# Main.net
KiCad netlist of a schematic drawn in EAGLE
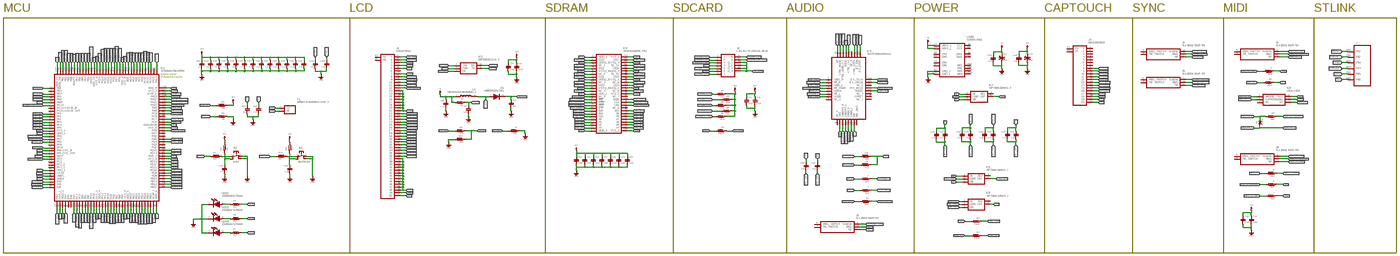
[diagram p0: schematic, sheet 1, overview]
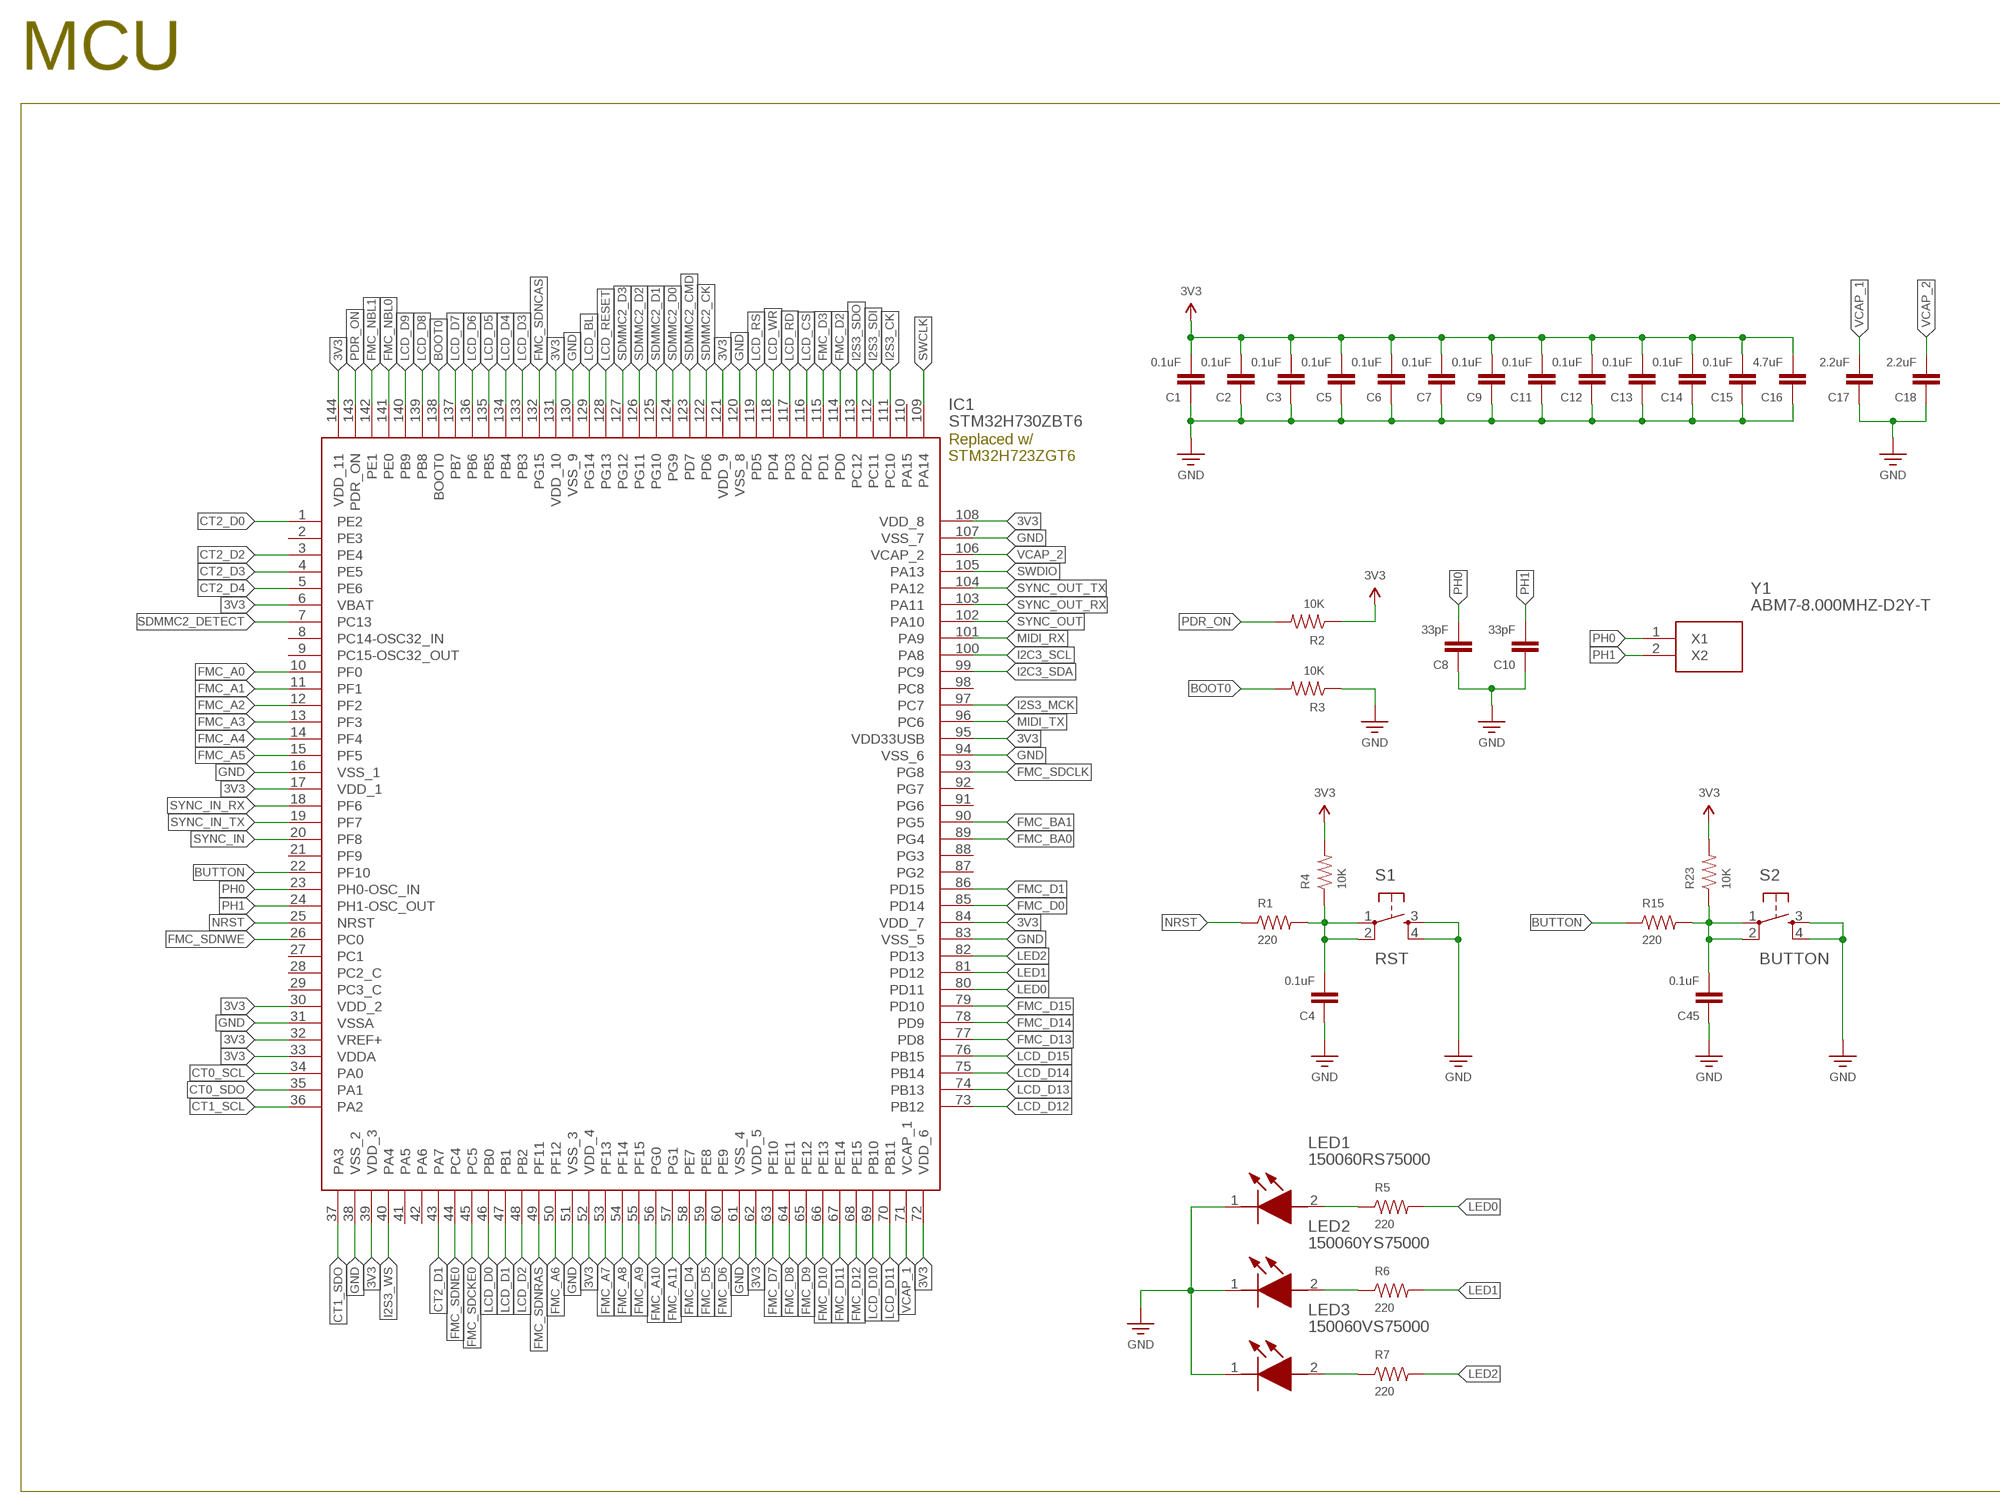
[diagram p1: schematic, sheet 1, part 1 of 4]
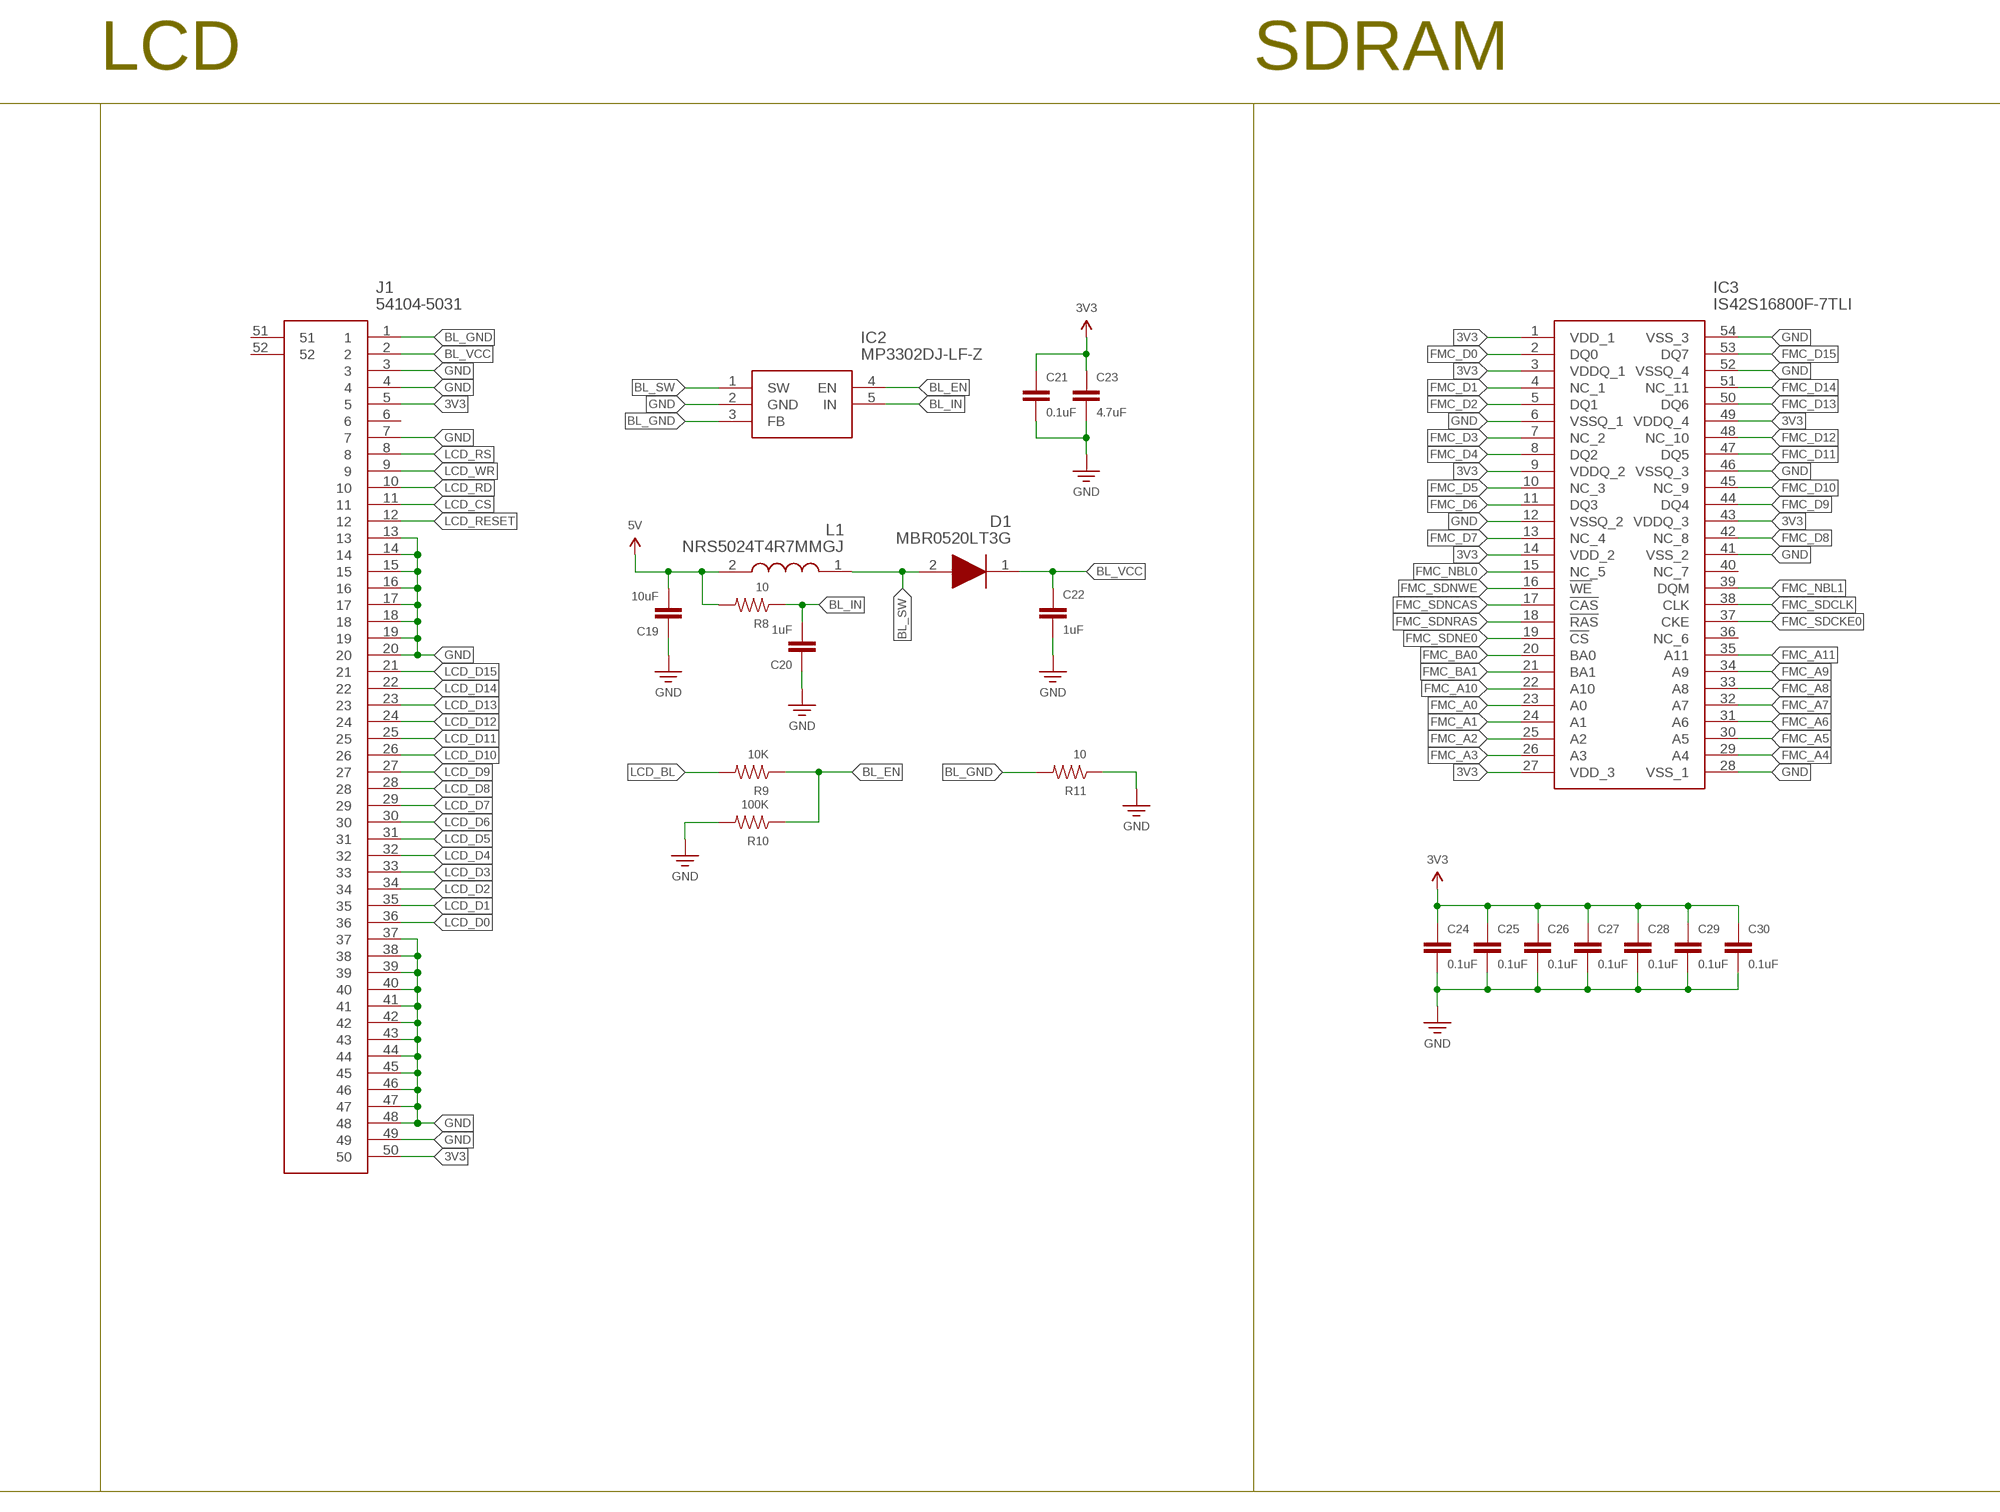
[diagram p2: schematic, sheet 1, part 2 of 4]
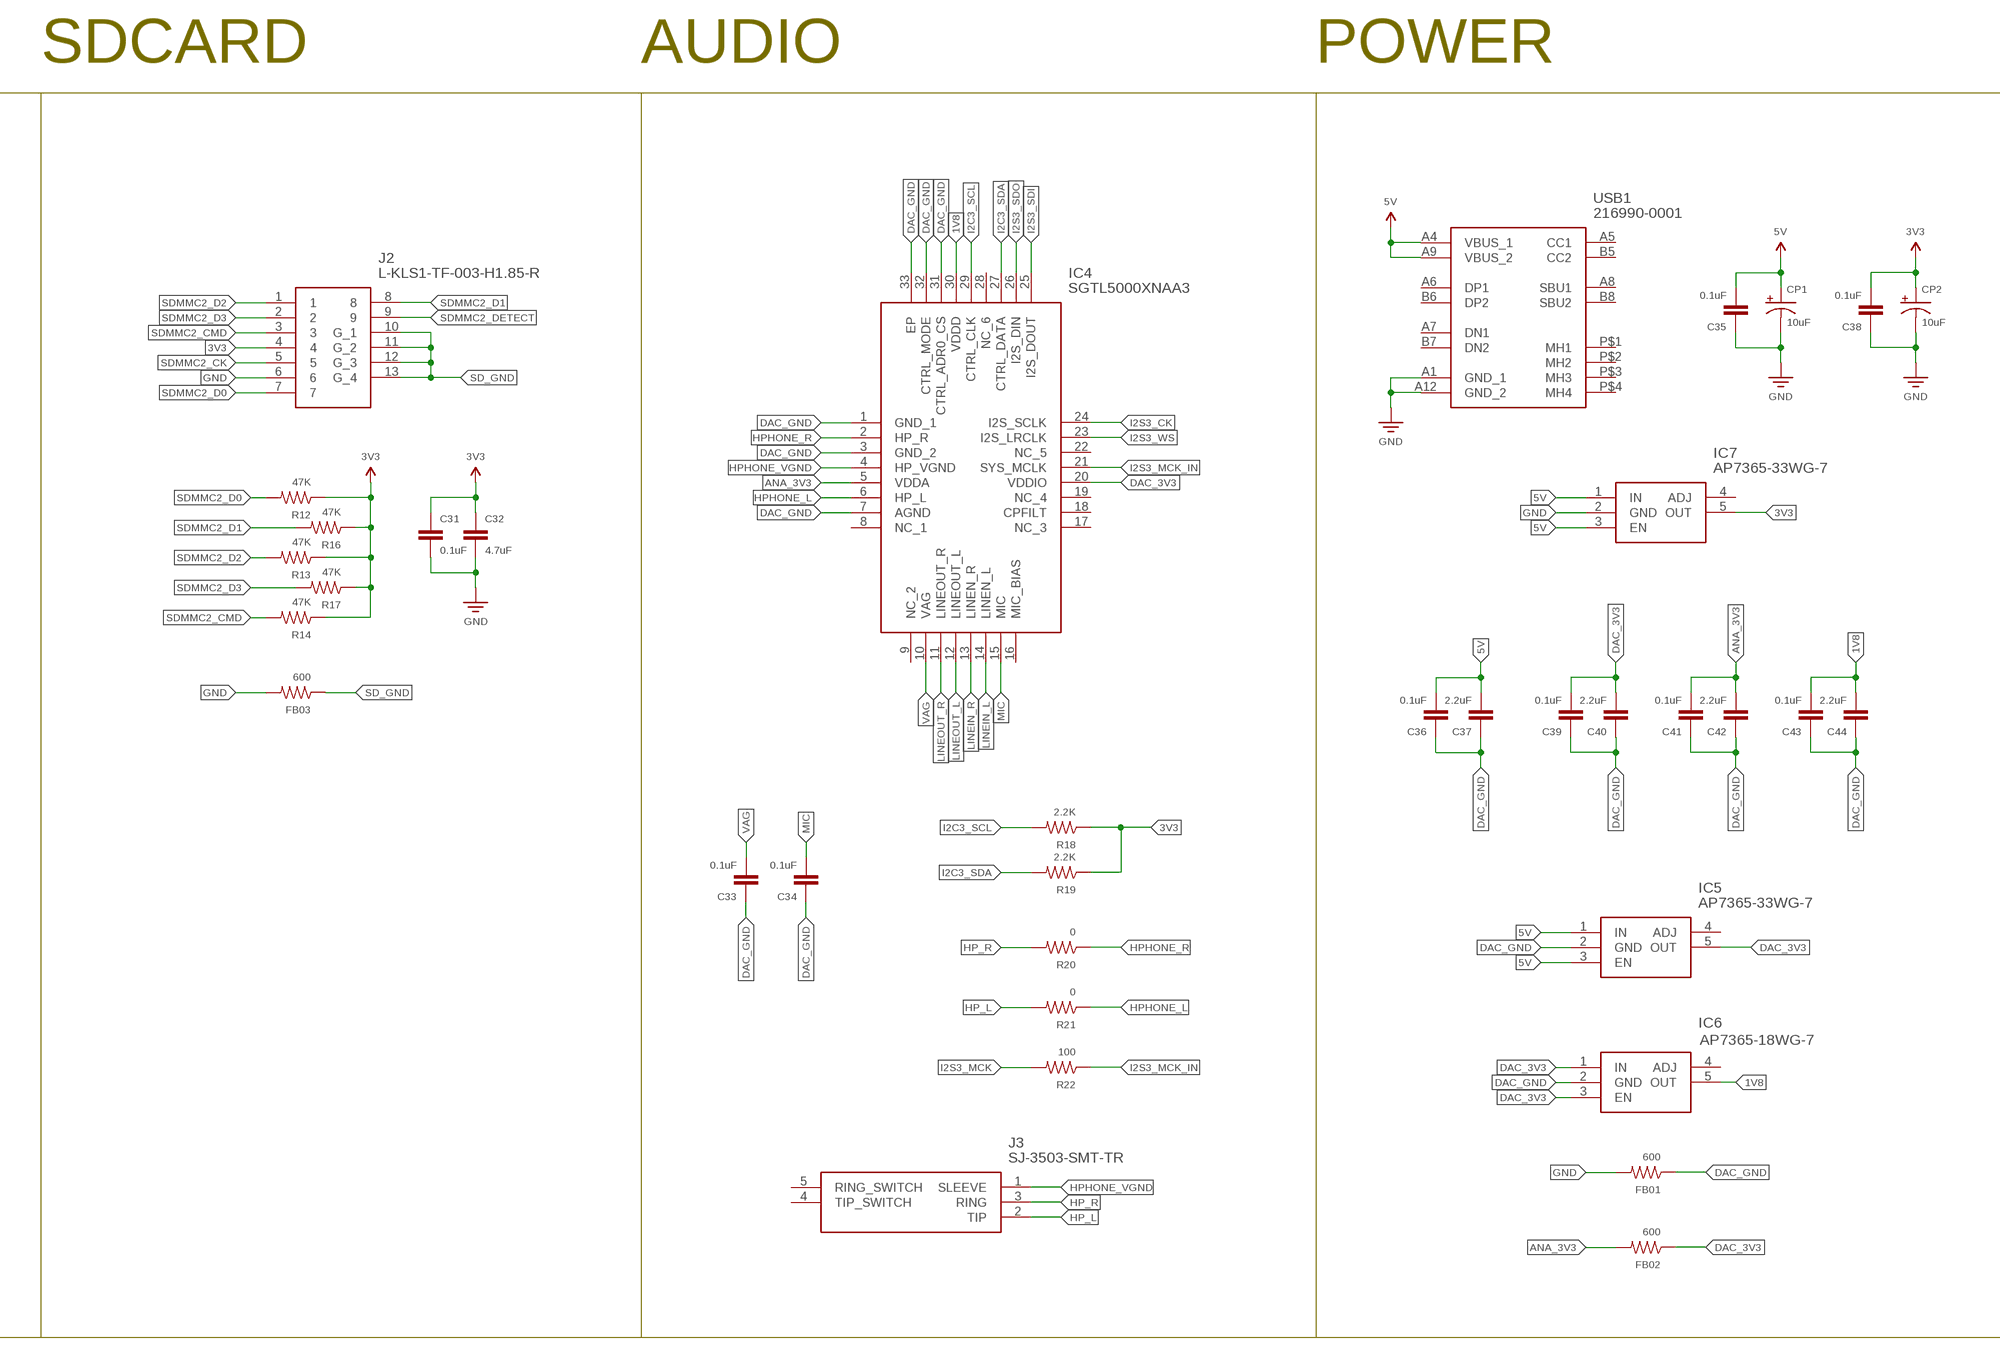
[diagram p3: schematic, sheet 1, part 3 of 4]
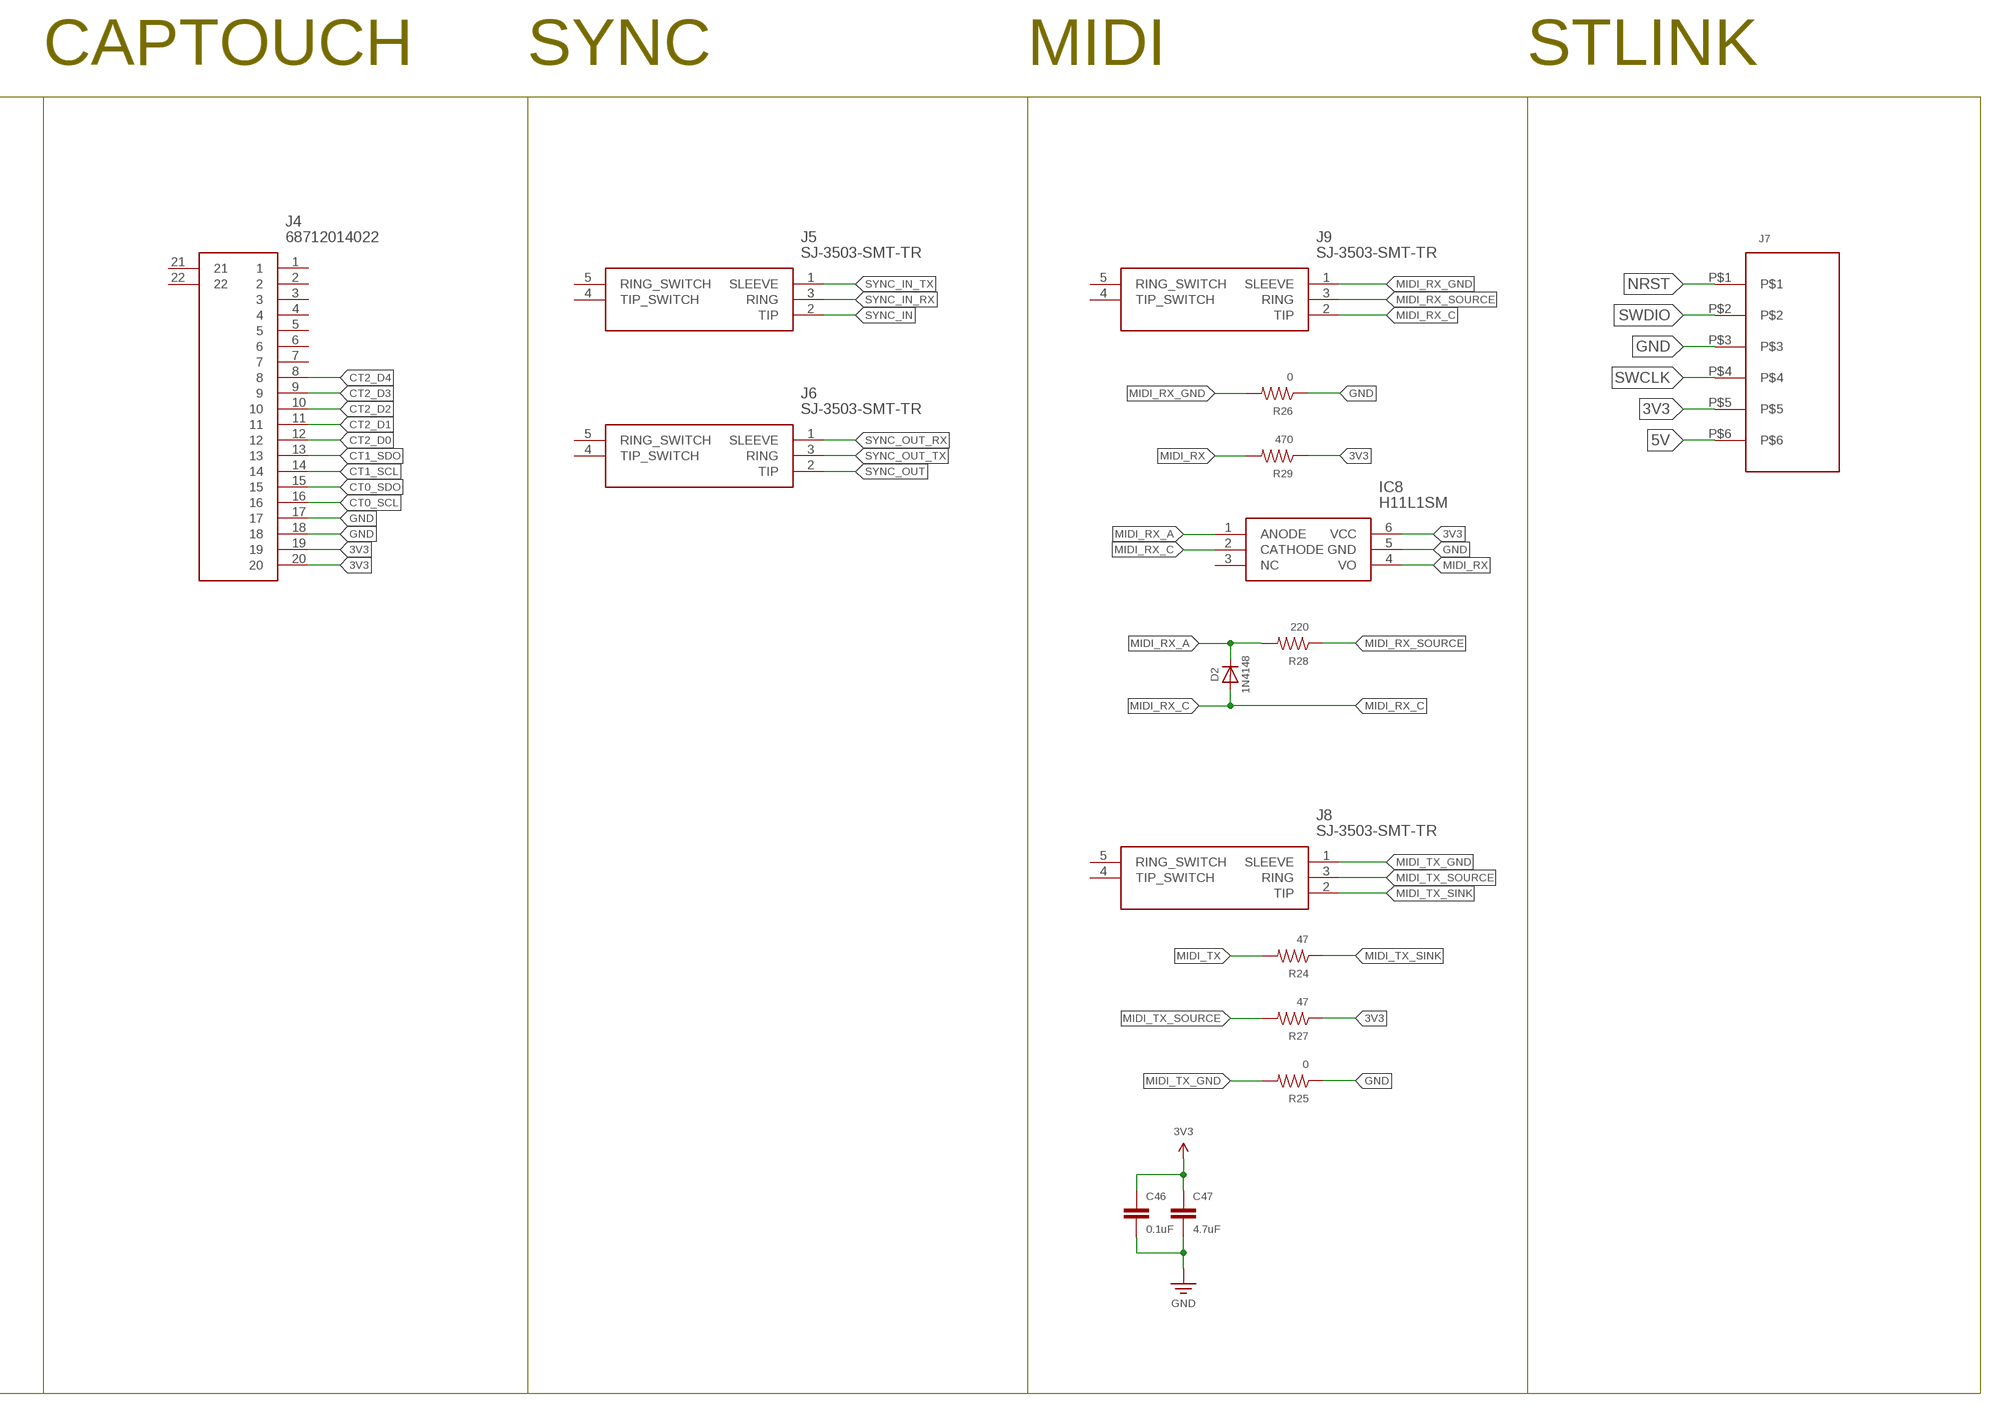
[diagram p4: schematic, sheet 1, part 4 of 4]

(export (version "E")
  (design (tool "Eeschema 10.0.6"))
  (components
    (comp (ref "C1")
      (value "0.1uF")
      (footprint "eagle-import:CAP-0603")
      (libsource (lib "eagle-import") (part "CAP-0603"))
    )
    (comp (ref "C2")
      (value "0.1uF")
      (footprint "eagle-import:CAP-0603")
      (libsource (lib "eagle-import") (part "CAP-0603"))
    )
    (comp (ref "C3")
      (value "0.1uF")
      (footprint "eagle-import:CAP-0603")
      (libsource (lib "eagle-import") (part "CAP-0603"))
    )
    (comp (ref "C4")
      (value "0.1uF")
      (footprint "eagle-import:CAP-0603")
      (libsource (lib "eagle-import") (part "CAP-0603"))
    )
    (comp (ref "C5")
      (value "0.1uF")
      (footprint "eagle-import:CAP-0603")
      (libsource (lib "eagle-import") (part "CAP-0603"))
    )
    (comp (ref "C6")
      (value "0.1uF")
      (footprint "eagle-import:CAP-0603")
      (libsource (lib "eagle-import") (part "CAP-0603"))
    )
    (comp (ref "C7")
      (value "0.1uF")
      (footprint "eagle-import:CAP-0603")
      (libsource (lib "eagle-import") (part "CAP-0603"))
    )
    (comp (ref "C8")
      (value "33pF")
      (footprint "eagle-import:CAP-0603")
      (libsource (lib "eagle-import") (part "CAP-0603"))
    )
    (comp (ref "C9")
      (value "0.1uF")
      (footprint "eagle-import:CAP-0603")
      (libsource (lib "eagle-import") (part "CAP-0603"))
    )
    (comp (ref "C10")
      (value "33pF")
      (footprint "eagle-import:CAP-0603")
      (libsource (lib "eagle-import") (part "CAP-0603"))
    )
    (comp (ref "C11")
      (value "0.1uF")
      (footprint "eagle-import:CAP-0603")
      (libsource (lib "eagle-import") (part "CAP-0603"))
    )
    (comp (ref "C12")
      (value "0.1uF")
      (footprint "eagle-import:CAP-0603")
      (libsource (lib "eagle-import") (part "CAP-0603"))
    )
    (comp (ref "C13")
      (value "0.1uF")
      (footprint "eagle-import:CAP-0603")
      (libsource (lib "eagle-import") (part "CAP-0603"))
    )
    (comp (ref "C14")
      (value "0.1uF")
      (footprint "eagle-import:CAP-0603")
      (libsource (lib "eagle-import") (part "CAP-0603"))
    )
    (comp (ref "C15")
      (value "0.1uF")
      (footprint "eagle-import:CAP-0603")
      (libsource (lib "eagle-import") (part "CAP-0603"))
    )
    (comp (ref "C16")
      (value "4.7uF")
      (footprint "eagle-import:CAP-0603")
      (libsource (lib "eagle-import") (part "CAP-0603"))
    )
    (comp (ref "C17")
      (value "2.2uF")
      (footprint "eagle-import:CAP-0603")
      (libsource (lib "eagle-import") (part "CAP-0603"))
    )
    (comp (ref "C18")
      (value "2.2uF")
      (footprint "eagle-import:CAP-0603")
      (libsource (lib "eagle-import") (part "CAP-0603"))
    )
    (comp (ref "C19")
      (value "10uF")
      (footprint "eagle-import:CAP-0603")
      (libsource (lib "eagle-import") (part "CAP-0603"))
    )
    (comp (ref "C20")
      (value "1uF")
      (footprint "eagle-import:CAP-0603")
      (libsource (lib "eagle-import") (part "CAP-0603"))
    )
    (comp (ref "C21")
      (value "0.1uF")
      (footprint "eagle-import:CAP-0603")
      (libsource (lib "eagle-import") (part "CAP-0603"))
    )
    (comp (ref "C22")
      (value "1uF")
      (footprint "eagle-import:CAP-0603")
      (libsource (lib "eagle-import") (part "CAP-0603"))
    )
    (comp (ref "C23")
      (value "4.7uF")
      (footprint "eagle-import:CAP-0603")
      (libsource (lib "eagle-import") (part "CAP-0603"))
    )
    (comp (ref "C24")
      (value "0.1uF")
      (footprint "eagle-import:CAP-0603")
      (libsource (lib "eagle-import") (part "CAP-0603"))
    )
    (comp (ref "C25")
      (value "0.1uF")
      (footprint "eagle-import:CAP-0603")
      (libsource (lib "eagle-import") (part "CAP-0603"))
    )
    (comp (ref "C26")
      (value "0.1uF")
      (footprint "eagle-import:CAP-0603")
      (libsource (lib "eagle-import") (part "CAP-0603"))
    )
    (comp (ref "C27")
      (value "0.1uF")
      (footprint "eagle-import:CAP-0603")
      (libsource (lib "eagle-import") (part "CAP-0603"))
    )
    (comp (ref "C28")
      (value "0.1uF")
      (footprint "eagle-import:CAP-0603")
      (libsource (lib "eagle-import") (part "CAP-0603"))
    )
    (comp (ref "C29")
      (value "0.1uF")
      (footprint "eagle-import:CAP-0603")
      (libsource (lib "eagle-import") (part "CAP-0603"))
    )
    (comp (ref "C30")
      (value "0.1uF")
      (footprint "eagle-import:CAP-0603")
      (libsource (lib "eagle-import") (part "CAP-0603"))
    )
    (comp (ref "C31")
      (value "0.1uF")
      (footprint "eagle-import:CAP-0603")
      (libsource (lib "eagle-import") (part "CAP-0603"))
    )
    (comp (ref "C32")
      (value "4.7uF")
      (footprint "eagle-import:CAP-0603")
      (libsource (lib "eagle-import") (part "CAP-0603"))
    )
    (comp (ref "C33")
      (value "0.1uF")
      (footprint "eagle-import:CAP-0603")
      (libsource (lib "eagle-import") (part "CAP-0603"))
    )
    (comp (ref "C34")
      (value "0.1uF")
      (footprint "eagle-import:CAP-0603")
      (libsource (lib "eagle-import") (part "CAP-0603"))
    )
    (comp (ref "C35")
      (value "0.1uF")
      (footprint "eagle-import:CAP-0603")
      (libsource (lib "eagle-import") (part "CAP-0603"))
    )
    (comp (ref "C36")
      (value "0.1uF")
      (footprint "eagle-import:CAP-0603")
      (libsource (lib "eagle-import") (part "CAP-0603"))
    )
    (comp (ref "C37")
      (value "2.2uF")
      (footprint "eagle-import:CAP-0603")
      (libsource (lib "eagle-import") (part "CAP-0603"))
    )
    (comp (ref "C38")
      (value "0.1uF")
      (footprint "eagle-import:CAP-0603")
      (libsource (lib "eagle-import") (part "CAP-0603"))
    )
    (comp (ref "C39")
      (value "0.1uF")
      (footprint "eagle-import:CAP-0603")
      (libsource (lib "eagle-import") (part "CAP-0603"))
    )
    (comp (ref "C40")
      (value "2.2uF")
      (footprint "eagle-import:CAP-0603")
      (libsource (lib "eagle-import") (part "CAP-0603"))
    )
    (comp (ref "C41")
      (value "0.1uF")
      (footprint "eagle-import:CAP-0603")
      (libsource (lib "eagle-import") (part "CAP-0603"))
    )
    (comp (ref "C42")
      (value "2.2uF")
      (footprint "eagle-import:CAP-0603")
      (libsource (lib "eagle-import") (part "CAP-0603"))
    )
    (comp (ref "C43")
      (value "0.1uF")
      (footprint "eagle-import:CAP-0603")
      (libsource (lib "eagle-import") (part "CAP-0603"))
    )
    (comp (ref "C44")
      (value "2.2uF")
      (footprint "eagle-import:CAP-0603")
      (libsource (lib "eagle-import") (part "CAP-0603"))
    )
    (comp (ref "C45")
      (value "0.1uF")
      (footprint "eagle-import:CAP-0603")
      (libsource (lib "eagle-import") (part "CAP-0603"))
    )
    (comp (ref "C46")
      (value "0.1uF")
      (footprint "eagle-import:CAP-0603")
      (libsource (lib "eagle-import") (part "CAP-0603"))
    )
    (comp (ref "C47")
      (value "4.7uF")
      (footprint "eagle-import:CAP-0603")
      (libsource (lib "eagle-import") (part "CAP-0603"))
    )
    (comp (ref "CP1")
      (value "10uF")
      (footprint "eagle-import:CAP-POL-1206")
      (libsource (lib "eagle-import") (part "CAP-POL-1206"))
    )
    (comp (ref "CP2")
      (value "10uF")
      (footprint "eagle-import:CAP-POL-1206")
      (libsource (lib "eagle-import") (part "CAP-POL-1206"))
    )
    (comp (ref "D1")
      (value "MBR0520LT3G")
      (footprint "eagle-import:SOD3716X135N")
      (fields (field (name "MOUSER_PART_NUMBER") "863-MBR0520LT3G"))
      (libsource (lib "eagle-import") (part "MBR0520LT3G"))
    )
    (comp (ref "D2")
      (value "1N4148")
      (footprint "eagle-import:SOD-323")
      (libsource (lib "eagle-import") (part "DIODESOD-323"))
    )
    (comp (ref "FB01")
      (value "600")
      (footprint "eagle-import:RES-0603")
      (libsource (lib "eagle-import") (part "RES-0603"))
    )
    (comp (ref "FB02")
      (value "600")
      (footprint "eagle-import:RES-0603")
      (libsource (lib "eagle-import") (part "RES-0603"))
    )
    (comp (ref "FB03")
      (value "600")
      (footprint "eagle-import:RES-0603")
      (libsource (lib "eagle-import") (part "RES-0603"))
    )
    (comp (ref "IC1")
      (value "STM32H730ZBT6")
      (footprint "eagle-import:QFP50P2200X2200X160-144N")
      (fields (field (name "MOUSER_PART_NUMBER") "511-STM32H730ZBT6"))
      (libsource (lib "eagle-import") (part "STM32H730ZBT6"))
    )
    (comp (ref "IC2")
      (value "MP3302DJ-LF-Z")
      (footprint "eagle-import:SOT95P280X100-5N")
      (fields (field (name "MOUSER_PART_NUMBER") "946-MP3302DJLFZ"))
      (libsource (lib "eagle-import") (part "MP3302DJ-LF-Z"))
    )
    (comp (ref "IC3")
      (value "IS42S16800F-7TLI")
      (footprint "eagle-import:SOP80P1176X120-54N")
      (fields (field (name "MOUSER_PART_NUMBER") "870-IS42S16800F-7TLI"))
      (libsource (lib "eagle-import") (part "IS42S16800F-7TLI"))
    )
    (comp (ref "IC4")
      (value "SGTL5000XNAA3")
      (footprint "eagle-import:QFN50P500X500X90-33N")
      (fields (field (name "MOUSER_PART_NUMBER") "841-SGTL5000XNAA3"))
      (libsource (lib "eagle-import") (part "SGTL5000XNAA3"))
    )
    (comp (ref "IC5")
      (value "AP7365-33WG-7")
      (footprint "eagle-import:SOT95P285X130-5N")
      (fields (field (name "MOUSER_PART_NUMBER") "621-AP7365-33WG-7"))
      (libsource (lib "eagle-import") (part "AP7365-33WG-7"))
    )
    (comp (ref "IC6")
      (value "AP7365-18WG-7")
      (footprint "eagle-import:SOT95P285X130-5N")
      (fields
        (field (name "ARROW_PART_NUMBER") "AP7365-33WG-7")
        (field (name "MOUSER_PART_NUMBER") "621-AP7365-33WG-7")
      )
      (libsource (lib "eagle-import") (part "AP7365-18WG-7"))
    )
    (comp (ref "IC7")
      (value "AP7365-33WG-7")
      (footprint "eagle-import:SOT95P285X130-5N")
      (fields (field (name "MOUSER_PART_NUMBER") "621-AP7365-33WG-7"))
      (libsource (lib "eagle-import") (part "AP7365-33WG-7"))
    )
    (comp (ref "IC8")
      (value "H11L1SM")
      (footprint "eagle-import:SMT-6PIN-(LEAD-BEND)")
      (fields (field (name "MOUSER_PART_NUMBER") "512-H11L1SM"))
      (libsource (lib "eagle-import") (part "H11L1SM"))
    )
    (comp (ref "J1")
      (value "54104-5031")
      (footprint "eagle-import:541045031")
      (fields (field (name "MOUSER_PART_NUMBER") "538-54104-5031"))
      (libsource (lib "eagle-import") (part "54104-5031"))
    )
    (comp (ref "J2")
      (value "L-KLS1-TF-003-H1.85-R")
      (footprint "eagle-import:L-KLS1-TF-003-H1.85-R")
      (libsource (lib "eagle-import") (part "L-KLS1-TF-003-H1.85-R"))
    )
    (comp (ref "J3")
      (value "SJ-3503-SMT-TR")
      (footprint "eagle-import:SJ3503SMTTR")
      (fields (field (name "MOUSER_PART_NUMBER") "490-SJ-3503-SMT-TR"))
      (libsource (lib "eagle-import") (part "SJ-3503-SMT-TR"))
    )
    (comp (ref "J4")
      (value "68712014022")
      (footprint "eagle-import:68712014022")
      (fields (field (name "MOUSER_PART_NUMBER") "710-68712014022"))
      (libsource (lib "eagle-import") (part "68712014022"))
    )
    (comp (ref "J5")
      (value "SJ-3503-SMT-TR")
      (footprint "eagle-import:SJ3503SMTTR")
      (fields (field (name "MOUSER_PART_NUMBER") "490-SJ-3503-SMT-TR"))
      (libsource (lib "eagle-import") (part "SJ-3503-SMT-TR"))
    )
    (comp (ref "J6")
      (value "SJ-3503-SMT-TR")
      (footprint "eagle-import:SJ3503SMTTR")
      (fields (field (name "MOUSER_PART_NUMBER") "490-SJ-3503-SMT-TR"))
      (libsource (lib "eagle-import") (part "SJ-3503-SMT-TR"))
    )
    (comp (ref "J7")
      (value "HFW6R-2STE1LF")
      (footprint "eagle-import:HFW6R-2STE1LF")
      (libsource (lib "eagle-import") (part "HFW6R-2STE1LF"))
    )
    (comp (ref "J8")
      (value "SJ-3503-SMT-TR")
      (footprint "eagle-import:SJ3503SMTTR")
      (fields (field (name "MOUSER_PART_NUMBER") "490-SJ-3503-SMT-TR"))
      (libsource (lib "eagle-import") (part "SJ-3503-SMT-TR"))
    )
    (comp (ref "J9")
      (value "SJ-3503-SMT-TR")
      (footprint "eagle-import:SJ3503SMTTR")
      (fields (field (name "MOUSER_PART_NUMBER") "490-SJ-3503-SMT-TR"))
      (libsource (lib "eagle-import") (part "SJ-3503-SMT-TR"))
    )
    (comp (ref "L1")
      (value "NRS5024T4R7MMGJ")
      (footprint "eagle-import:NRS5024T4R7MMGJ")
      (fields (field (name "MOUSER_PART_NUMBER") "963-NRS5024T4R7MMGJ"))
      (libsource (lib "eagle-import") (part "NRS5024T4R7MMGJ"))
    )
    (comp (ref "LED1")
      (value "150060RS75000")
      (footprint "eagle-import:LEDC1608X80N")
      (fields (field (name "MOUSER_PART_NUMBER") "710-150060RS75000"))
      (libsource (lib "eagle-import") (part "150060RS75000"))
    )
    (comp (ref "LED2")
      (value "150060YS75000")
      (footprint "eagle-import:LEDC1608X80N")
      (fields (field (name "MOUSER_PART_NUMBER") "710-150060YS75000"))
      (libsource (lib "eagle-import") (part "150060YS75000"))
    )
    (comp (ref "LED3")
      (value "150060VS75000")
      (footprint "eagle-import:LEDC1608X80N")
      (fields (field (name "MOUSER_PART_NUMBER") "710-150060VS75000"))
      (libsource (lib "eagle-import") (part "150060VS75000"))
    )
    (comp (ref "R1")
      (value "220")
      (footprint "eagle-import:RES-0603")
      (libsource (lib "eagle-import") (part "RES-0603"))
    )
    (comp (ref "R2")
      (value "10K")
      (footprint "eagle-import:RES-0603")
      (libsource (lib "eagle-import") (part "RES-0603"))
    )
    (comp (ref "R3")
      (value "10K")
      (footprint "eagle-import:RES-0603")
      (libsource (lib "eagle-import") (part "RES-0603"))
    )
    (comp (ref "R4")
      (value "10K")
      (footprint "eagle-import:RES-0603")
      (libsource (lib "eagle-import") (part "RES-0603"))
    )
    (comp (ref "R5")
      (value "220")
      (footprint "eagle-import:RES-0603")
      (libsource (lib "eagle-import") (part "RES-0603"))
    )
    (comp (ref "R6")
      (value "220")
      (footprint "eagle-import:RES-0603")
      (libsource (lib "eagle-import") (part "RES-0603"))
    )
    (comp (ref "R7")
      (value "220")
      (footprint "eagle-import:RES-0603")
      (libsource (lib "eagle-import") (part "RES-0603"))
    )
    (comp (ref "R8")
      (value "10")
      (footprint "eagle-import:RES-0603")
      (libsource (lib "eagle-import") (part "RES-0603"))
    )
    (comp (ref "R9")
      (value "10K")
      (footprint "eagle-import:RES-0603")
      (libsource (lib "eagle-import") (part "RES-0603"))
    )
    (comp (ref "R10")
      (value "100K")
      (footprint "eagle-import:RES-0603")
      (libsource (lib "eagle-import") (part "RES-0603"))
    )
    (comp (ref "R11")
      (value "10")
      (footprint "eagle-import:RES-0603")
      (libsource (lib "eagle-import") (part "RES-0603"))
    )
    (comp (ref "R12")
      (value "47K")
      (footprint "eagle-import:RES-0603")
      (libsource (lib "eagle-import") (part "RES-0603"))
    )
    (comp (ref "R13")
      (value "47K")
      (footprint "eagle-import:RES-0603")
      (libsource (lib "eagle-import") (part "RES-0603"))
    )
    (comp (ref "R14")
      (value "47K")
      (footprint "eagle-import:RES-0603")
      (libsource (lib "eagle-import") (part "RES-0603"))
    )
    (comp (ref "R15")
      (value "220")
      (footprint "eagle-import:RES-0603")
      (libsource (lib "eagle-import") (part "RES-0603"))
    )
    (comp (ref "R16")
      (value "47K")
      (footprint "eagle-import:RES-0603")
      (libsource (lib "eagle-import") (part "RES-0603"))
    )
    (comp (ref "R17")
      (value "47K")
      (footprint "eagle-import:RES-0603")
      (libsource (lib "eagle-import") (part "RES-0603"))
    )
    (comp (ref "R18")
      (value "2.2K")
      (footprint "eagle-import:RES-0603")
      (libsource (lib "eagle-import") (part "RES-0603"))
    )
    (comp (ref "R19")
      (value "2.2K")
      (footprint "eagle-import:RES-0603")
      (libsource (lib "eagle-import") (part "RES-0603"))
    )
    (comp (ref "R20")
      (value "0")
      (footprint "eagle-import:RES-0603")
      (libsource (lib "eagle-import") (part "RES-0603"))
    )
    (comp (ref "R21")
      (value "0")
      (footprint "eagle-import:RES-0603")
      (libsource (lib "eagle-import") (part "RES-0603"))
    )
    (comp (ref "R22")
      (value "100")
      (footprint "eagle-import:RES-0603")
      (libsource (lib "eagle-import") (part "RES-0603"))
    )
    (comp (ref "R23")
      (value "10K")
      (footprint "eagle-import:RES-0603")
      (libsource (lib "eagle-import") (part "RES-0603"))
    )
    (comp (ref "R24")
      (value "47")
      (footprint "eagle-import:RES-0603")
      (libsource (lib "eagle-import") (part "RES-0603"))
    )
    (comp (ref "R25")
      (value "0")
      (footprint "eagle-import:RES-0603")
      (libsource (lib "eagle-import") (part "RES-0603"))
    )
    (comp (ref "R26")
      (value "0")
      (footprint "eagle-import:RES-0603")
      (libsource (lib "eagle-import") (part "RES-0603"))
    )
    (comp (ref "R27")
      (value "47")
      (footprint "eagle-import:RES-0603")
      (libsource (lib "eagle-import") (part "RES-0603"))
    )
    (comp (ref "R28")
      (value "220")
      (footprint "eagle-import:RES-0603")
      (libsource (lib "eagle-import") (part "RES-0603"))
    )
    (comp (ref "R29")
      (value "470")
      (footprint "eagle-import:RES-0603")
      (libsource (lib "eagle-import") (part "RES-0603"))
    )
    (comp (ref "S1")
      (value "RST")
      (footprint "eagle-import:TACTILE-SWITCH-SMD")
      (libsource (lib "eagle-import") (part "TAC_SWITCHSMD"))
    )
    (comp (ref "S2")
      (value "BUTTON")
      (footprint "eagle-import:TACTILE-SWITCH-SMD")
      (libsource (lib "eagle-import") (part "TAC_SWITCHSMD"))
    )
    (comp (ref "USB1")
      (value "216990-0001")
      (footprint "eagle-import:2169900001")
      (fields (field (name "MOUSER_PART_NUMBER") "538-216990-0001"))
      (libsource (lib "eagle-import") (part "216990-0001"))
    )
    (comp (ref "Y1")
      (value "ABM7-8.000MHZ-D2Y-T")
      (footprint "eagle-import:ABM78000MHZD2YT")
      (fields (field (name "MOUSER_PART_NUMBER") "815-ABM7-8-D2Y-T"))
      (libsource (lib "eagle-import") (part "ABM7-8.000MHZ-D2Y-T"))
    )
  )
  (nets
    (net (code "1") (name "1V8") (class "Default")
      (node (ref "C43") (pin "P$2") (pinfunction "2_P$2") (pintype "passive"))
      (node (ref "C44") (pin "P$2") (pinfunction "2_P$2") (pintype "passive"))
      (node (ref "IC4") (pin "30") (pinfunction "VDDD_30") (pintype "bidirectional"))
      (node (ref "IC6") (pin "5") (pinfunction "OUT_5") (pintype "bidirectional"))
    )
    (net (code "2") (name "3V3") (class "Default")
      (node (ref "C1") (pin "P$2") (pinfunction "2_P$2") (pintype "passive"))
      (node (ref "C11") (pin "P$2") (pinfunction "2_P$2") (pintype "passive"))
      (node (ref "C12") (pin "P$2") (pinfunction "2_P$2") (pintype "passive"))
      (node (ref "C13") (pin "P$2") (pinfunction "2_P$2") (pintype "passive"))
      (node (ref "C14") (pin "P$2") (pinfunction "2_P$2") (pintype "passive"))
      (node (ref "C15") (pin "P$2") (pinfunction "2_P$2") (pintype "passive"))
      (node (ref "C16") (pin "P$2") (pinfunction "2_P$2") (pintype "passive"))
      (node (ref "C2") (pin "P$2") (pinfunction "2_P$2") (pintype "passive"))
      (node (ref "C21") (pin "P$1") (pinfunction "1_P$1") (pintype "passive"))
      (node (ref "C23") (pin "P$1") (pinfunction "1_P$1") (pintype "passive"))
      (node (ref "C24") (pin "P$1") (pinfunction "1_P$1") (pintype "passive"))
      (node (ref "C25") (pin "P$1") (pinfunction "1_P$1") (pintype "passive"))
      (node (ref "C26") (pin "P$1") (pinfunction "1_P$1") (pintype "passive"))
      (node (ref "C27") (pin "P$1") (pinfunction "1_P$1") (pintype "passive"))
      (node (ref "C28") (pin "P$1") (pinfunction "1_P$1") (pintype "passive"))
      (node (ref "C29") (pin "P$1") (pinfunction "1_P$1") (pintype "passive"))
      (node (ref "C3") (pin "P$2") (pinfunction "2_P$2") (pintype "passive"))
      (node (ref "C30") (pin "P$1") (pinfunction "1_P$1") (pintype "passive"))
      (node (ref "C31") (pin "P$1") (pinfunction "1_P$1") (pintype "passive"))
      (node (ref "C32") (pin "P$1") (pinfunction "1_P$1") (pintype "passive"))
      (node (ref "C38") (pin "P$2") (pinfunction "2_P$2") (pintype "passive"))
      (node (ref "C46") (pin "P$1") (pinfunction "1_P$1") (pintype "passive"))
      (node (ref "C47") (pin "P$1") (pinfunction "1_P$1") (pintype "passive"))
      (node (ref "C5") (pin "P$2") (pinfunction "2_P$2") (pintype "passive"))
      (node (ref "C6") (pin "P$2") (pinfunction "2_P$2") (pintype "passive"))
      (node (ref "C7") (pin "P$2") (pinfunction "2_P$2") (pintype "passive"))
      (node (ref "C9") (pin "P$2") (pinfunction "2_P$2") (pintype "passive"))
      (node (ref "CP2") (pin "P$1") (pinfunction "+_P$1") (pintype "passive"))
      (node (ref "IC1") (pin "108") (pinfunction "VDD_8_108") (pintype "bidirectional"))
      (node (ref "IC1") (pin "121") (pinfunction "VDD_9_121") (pintype "bidirectional"))
      (node (ref "IC1") (pin "131") (pinfunction "VDD_10_131") (pintype "bidirectional"))
      (node (ref "IC1") (pin "144") (pinfunction "VDD_11_144") (pintype "bidirectional"))
      (node (ref "IC1") (pin "17") (pinfunction "VDD_1_17") (pintype "bidirectional"))
      (node (ref "IC1") (pin "30") (pinfunction "VDD_2_30") (pintype "bidirectional"))
      (node (ref "IC1") (pin "32") (pinfunction "VREF+_32") (pintype "bidirectional"))
      (node (ref "IC1") (pin "33") (pinfunction "VDDA_33") (pintype "bidirectional"))
      (node (ref "IC1") (pin "39") (pinfunction "VDD_3_39") (pintype "bidirectional"))
      (node (ref "IC1") (pin "52") (pinfunction "VDD_4_52") (pintype "bidirectional"))
      (node (ref "IC1") (pin "6") (pinfunction "VBAT_6") (pintype "bidirectional"))
      (node (ref "IC1") (pin "62") (pinfunction "VDD_5_62") (pintype "bidirectional"))
      (node (ref "IC1") (pin "72") (pinfunction "VDD_6_72") (pintype "bidirectional"))
      (node (ref "IC1") (pin "84") (pinfunction "VDD_7_84") (pintype "bidirectional"))
      (node (ref "IC1") (pin "95") (pinfunction "VDD33USB_95") (pintype "bidirectional"))
      (node (ref "IC3") (pin "1") (pinfunction "VDD_1_1") (pintype "bidirectional"))
      (node (ref "IC3") (pin "14") (pinfunction "VDD_2_14") (pintype "bidirectional"))
      (node (ref "IC3") (pin "27") (pinfunction "VDD_3_27") (pintype "bidirectional"))
      (node (ref "IC3") (pin "3") (pinfunction "VDDQ_1_3") (pintype "bidirectional"))
      (node (ref "IC3") (pin "43") (pinfunction "VDDQ_3_43") (pintype "bidirectional"))
      (node (ref "IC3") (pin "49") (pinfunction "VDDQ_4_49") (pintype "bidirectional"))
      (node (ref "IC3") (pin "9") (pinfunction "VDDQ_2_9") (pintype "bidirectional"))
      (node (ref "IC7") (pin "5") (pinfunction "OUT_5") (pintype "bidirectional"))
      (node (ref "IC8") (pin "6") (pinfunction "VCC_6") (pintype "bidirectional"))
      (node (ref "J1") (pin "5") (pinfunction "5_5") (pintype "bidirectional"))
      (node (ref "J1") (pin "50") (pinfunction "50_50") (pintype "bidirectional"))
      (node (ref "J2") (pin "4") (pinfunction "4_4") (pintype "bidirectional"))
      (node (ref "J4") (pin "19") (pinfunction "19_19") (pintype "bidirectional"))
      (node (ref "J4") (pin "20") (pinfunction "20_20") (pintype "bidirectional"))
      (node (ref "J7") (pin "P$5") (pinfunction "P$5_P$5") (pintype "bidirectional"))
      (node (ref "R12") (pin "P$1") (pinfunction "1_P$1") (pintype "passive"))
      (node (ref "R13") (pin "P$1") (pinfunction "1_P$1") (pintype "passive"))
      (node (ref "R14") (pin "P$1") (pinfunction "1_P$1") (pintype "passive"))
      (node (ref "R16") (pin "P$1") (pinfunction "1_P$1") (pintype "passive"))
      (node (ref "R17") (pin "P$1") (pinfunction "1_P$1") (pintype "passive"))
      (node (ref "R18") (pin "P$1") (pinfunction "1_P$1") (pintype "passive"))
      (node (ref "R19") (pin "P$1") (pinfunction "1_P$1") (pintype "passive"))
      (node (ref "R2") (pin "P$1") (pinfunction "1_P$1") (pintype "passive"))
      (node (ref "R23") (pin "P$2") (pinfunction "2_P$2") (pintype "passive"))
      (node (ref "R27") (pin "P$1") (pinfunction "1_P$1") (pintype "passive"))
      (node (ref "R29") (pin "P$1") (pinfunction "1_P$1") (pintype "passive"))
      (node (ref "R4") (pin "P$2") (pinfunction "2_P$2") (pintype "passive"))
    )
    (net (code "3") (name "5V") (class "Default")
      (node (ref "C19") (pin "P$2") (pinfunction "2_P$2") (pintype "passive"))
      (node (ref "C35") (pin "P$2") (pinfunction "2_P$2") (pintype "passive"))
      (node (ref "C36") (pin "P$2") (pinfunction "2_P$2") (pintype "passive"))
      (node (ref "C37") (pin "P$2") (pinfunction "2_P$2") (pintype "passive"))
      (node (ref "CP1") (pin "P$1") (pinfunction "+_P$1") (pintype "passive"))
      (node (ref "IC5") (pin "1") (pinfunction "IN_1") (pintype "bidirectional"))
      (node (ref "IC5") (pin "3") (pinfunction "EN_3") (pintype "bidirectional"))
      (node (ref "IC7") (pin "1") (pinfunction "IN_1") (pintype "bidirectional"))
      (node (ref "IC7") (pin "3") (pinfunction "EN_3") (pintype "bidirectional"))
      (node (ref "J7") (pin "P$6") (pinfunction "P$6_P$6") (pintype "bidirectional"))
      (node (ref "L1") (pin "2") (pinfunction "2_2") (pintype "bidirectional"))
      (node (ref "R8") (pin "P$2") (pinfunction "2_P$2") (pintype "passive"))
      (node (ref "USB1") (pin "A4") (pinfunction "VBUS_1_A4") (pintype "bidirectional"))
      (node (ref "USB1") (pin "A9") (pinfunction "VBUS_2_A9") (pintype "bidirectional"))
    )
    (net (code "4") (name "ANA_3V3") (class "Default")
      (node (ref "C41") (pin "P$2") (pinfunction "2_P$2") (pintype "passive"))
      (node (ref "C42") (pin "P$2") (pinfunction "2_P$2") (pintype "passive"))
      (node (ref "FB02") (pin "P$2") (pinfunction "2_P$2") (pintype "passive"))
      (node (ref "IC4") (pin "5") (pinfunction "VDDA_5") (pintype "bidirectional"))
    )
    (net (code "5") (name "BL_EN") (class "Default")
      (node (ref "IC2") (pin "4") (pinfunction "EN_4") (pintype "bidirectional"))
      (node (ref "R10") (pin "P$1") (pinfunction "1_P$1") (pintype "passive"))
      (node (ref "R9") (pin "P$1") (pinfunction "1_P$1") (pintype "passive"))
    )
    (net (code "6") (name "BL_GND") (class "Default")
      (node (ref "IC2") (pin "3") (pinfunction "FB_3") (pintype "bidirectional"))
      (node (ref "J1") (pin "1") (pinfunction "1_1") (pintype "bidirectional"))
      (node (ref "R11") (pin "P$2") (pinfunction "2_P$2") (pintype "passive"))
    )
    (net (code "7") (name "BL_IN") (class "Default")
      (node (ref "C20") (pin "P$2") (pinfunction "2_P$2") (pintype "passive"))
      (node (ref "IC2") (pin "5") (pinfunction "IN_5") (pintype "bidirectional"))
      (node (ref "R8") (pin "P$1") (pinfunction "1_P$1") (pintype "passive"))
    )
    (net (code "8") (name "BL_SW") (class "Default")
      (node (ref "D1") (pin "2") (pinfunction "A_2") (pintype "bidirectional"))
      (node (ref "IC2") (pin "1") (pinfunction "SW_1") (pintype "bidirectional"))
      (node (ref "L1") (pin "1") (pinfunction "1_1") (pintype "bidirectional"))
    )
    (net (code "9") (name "BL_VCC") (class "Default")
      (node (ref "C22") (pin "P$1") (pinfunction "1_P$1") (pintype "passive"))
      (node (ref "D1") (pin "1") (pinfunction "K_1") (pintype "bidirectional"))
      (node (ref "J1") (pin "2") (pinfunction "2_2") (pintype "bidirectional"))
    )
    (net (code "10") (name "BOOT0") (class "Default")
      (node (ref "IC1") (pin "138") (pinfunction "BOOT0_138") (pintype "bidirectional"))
      (node (ref "R3") (pin "P$2") (pinfunction "2_P$2") (pintype "passive"))
    )
    (net (code "11") (name "BUTTON") (class "Default")
      (node (ref "IC1") (pin "22") (pinfunction "PF10_22") (pintype "bidirectional"))
      (node (ref "R15") (pin "P$1") (pinfunction "1_P$1") (pintype "passive"))
    )
    (net (code "12") (name "CT0_SCL") (class "Default")
      (node (ref "IC1") (pin "34") (pinfunction "PA0_34") (pintype "bidirectional"))
      (node (ref "J4") (pin "16") (pinfunction "16_16") (pintype "bidirectional"))
    )
    (net (code "13") (name "CT0_SDO") (class "Default")
      (node (ref "IC1") (pin "35") (pinfunction "PA1_35") (pintype "bidirectional"))
      (node (ref "J4") (pin "15") (pinfunction "15_15") (pintype "bidirectional"))
    )
    (net (code "14") (name "CT1_SCL") (class "Default")
      (node (ref "IC1") (pin "36") (pinfunction "PA2_36") (pintype "bidirectional"))
      (node (ref "J4") (pin "14") (pinfunction "14_14") (pintype "bidirectional"))
    )
    (net (code "15") (name "CT1_SDO") (class "Default")
      (node (ref "IC1") (pin "37") (pinfunction "PA3_37") (pintype "bidirectional"))
      (node (ref "J4") (pin "13") (pinfunction "13_13") (pintype "bidirectional"))
    )
    (net (code "16") (name "CT2_D0") (class "Default")
      (node (ref "IC1") (pin "1") (pinfunction "PE2_1") (pintype "bidirectional"))
      (node (ref "J4") (pin "12") (pinfunction "12_12") (pintype "bidirectional"))
    )
    (net (code "17") (name "CT2_D1") (class "Default")
      (node (ref "IC1") (pin "43") (pinfunction "PA7_43") (pintype "bidirectional"))
      (node (ref "J4") (pin "11") (pinfunction "11_11") (pintype "bidirectional"))
    )
    (net (code "18") (name "CT2_D2") (class "Default")
      (node (ref "IC1") (pin "3") (pinfunction "PE4_3") (pintype "bidirectional"))
      (node (ref "J4") (pin "10") (pinfunction "10_10") (pintype "bidirectional"))
    )
    (net (code "19") (name "CT2_D3") (class "Default")
      (node (ref "IC1") (pin "4") (pinfunction "PE5_4") (pintype "bidirectional"))
      (node (ref "J4") (pin "9") (pinfunction "9_9") (pintype "bidirectional"))
    )
    (net (code "20") (name "CT2_D4") (class "Default")
      (node (ref "IC1") (pin "5") (pinfunction "PE6_5") (pintype "bidirectional"))
      (node (ref "J4") (pin "8") (pinfunction "8_8") (pintype "bidirectional"))
    )
    (net (code "21") (name "DAC_3V3") (class "Default")
      (node (ref "C39") (pin "P$2") (pinfunction "2_P$2") (pintype "passive"))
      (node (ref "C40") (pin "P$2") (pinfunction "2_P$2") (pintype "passive"))
      (node (ref "FB02") (pin "P$1") (pinfunction "1_P$1") (pintype "passive"))
      (node (ref "IC4") (pin "20") (pinfunction "VDDIO_20") (pintype "bidirectional"))
      (node (ref "IC5") (pin "5") (pinfunction "OUT_5") (pintype "bidirectional"))
      (node (ref "IC6") (pin "1") (pinfunction "IN_1") (pintype "bidirectional"))
      (node (ref "IC6") (pin "3") (pinfunction "EN_3") (pintype "bidirectional"))
    )
    (net (code "22") (name "DAC_GND") (class "Default")
      (node (ref "C33") (pin "P$1") (pinfunction "1_P$1") (pintype "passive"))
      (node (ref "C34") (pin "P$1") (pinfunction "1_P$1") (pintype "passive"))
      (node (ref "C36") (pin "P$1") (pinfunction "1_P$1") (pintype "passive"))
      (node (ref "C37") (pin "P$1") (pinfunction "1_P$1") (pintype "passive"))
      (node (ref "C39") (pin "P$1") (pinfunction "1_P$1") (pintype "passive"))
      (node (ref "C40") (pin "P$1") (pinfunction "1_P$1") (pintype "passive"))
      (node (ref "C41") (pin "P$1") (pinfunction "1_P$1") (pintype "passive"))
      (node (ref "C42") (pin "P$1") (pinfunction "1_P$1") (pintype "passive"))
      (node (ref "C43") (pin "P$1") (pinfunction "1_P$1") (pintype "passive"))
      (node (ref "C44") (pin "P$1") (pinfunction "1_P$1") (pintype "passive"))
      (node (ref "FB01") (pin "P$1") (pinfunction "1_P$1") (pintype "passive"))
      (node (ref "IC4") (pin "1") (pinfunction "GND_1_1") (pintype "bidirectional"))
      (node (ref "IC4") (pin "3") (pinfunction "GND_2_3") (pintype "bidirectional"))
      (node (ref "IC4") (pin "31") (pinfunction "CTRL_ADR0_CS_31") (pintype "bidirectional"))
      (node (ref "IC4") (pin "32") (pinfunction "CTRL_MODE_32") (pintype "bidirectional"))
      (node (ref "IC4") (pin "33") (pinfunction "EP_33") (pintype "bidirectional"))
      (node (ref "IC4") (pin "7") (pinfunction "AGND_7") (pintype "bidirectional"))
      (node (ref "IC5") (pin "2") (pinfunction "GND_2") (pintype "bidirectional"))
      (node (ref "IC6") (pin "2") (pinfunction "GND_2") (pintype "bidirectional"))
    )
    (net (code "23") (name "FMC_A0") (class "Default")
      (node (ref "IC1") (pin "10") (pinfunction "PF0_10") (pintype "bidirectional"))
      (node (ref "IC3") (pin "23") (pinfunction "A0_23") (pintype "bidirectional"))
    )
    (net (code "24") (name "FMC_A1") (class "Default")
      (node (ref "IC1") (pin "11") (pinfunction "PF1_11") (pintype "bidirectional"))
      (node (ref "IC3") (pin "24") (pinfunction "A1_24") (pintype "bidirectional"))
    )
    (net (code "25") (name "FMC_A2") (class "Default")
      (node (ref "IC1") (pin "12") (pinfunction "PF2_12") (pintype "bidirectional"))
      (node (ref "IC3") (pin "25") (pinfunction "A2_25") (pintype "bidirectional"))
    )
    (net (code "26") (name "FMC_A3") (class "Default")
      (node (ref "IC1") (pin "13") (pinfunction "PF3_13") (pintype "bidirectional"))
      (node (ref "IC3") (pin "26") (pinfunction "A3_26") (pintype "bidirectional"))
    )
    (net (code "27") (name "FMC_A4") (class "Default")
      (node (ref "IC1") (pin "14") (pinfunction "PF4_14") (pintype "bidirectional"))
      (node (ref "IC3") (pin "29") (pinfunction "A4_29") (pintype "bidirectional"))
    )
    (net (code "28") (name "FMC_A5") (class "Default")
      (node (ref "IC1") (pin "15") (pinfunction "PF5_15") (pintype "bidirectional"))
      (node (ref "IC3") (pin "30") (pinfunction "A5_30") (pintype "bidirectional"))
    )
    (net (code "29") (name "FMC_A6") (class "Default")
      (node (ref "IC1") (pin "50") (pinfunction "PF12_50") (pintype "bidirectional"))
      (node (ref "IC3") (pin "31") (pinfunction "A6_31") (pintype "bidirectional"))
    )
    (net (code "30") (name "FMC_A7") (class "Default")
      (node (ref "IC1") (pin "53") (pinfunction "PF13_53") (pintype "bidirectional"))
      (node (ref "IC3") (pin "32") (pinfunction "A7_32") (pintype "bidirectional"))
    )
    (net (code "31") (name "FMC_A8") (class "Default")
      (node (ref "IC1") (pin "54") (pinfunction "PF14_54") (pintype "bidirectional"))
      (node (ref "IC3") (pin "33") (pinfunction "A8_33") (pintype "bidirectional"))
    )
    (net (code "32") (name "FMC_A9") (class "Default")
      (node (ref "IC1") (pin "55") (pinfunction "PF15_55") (pintype "bidirectional"))
      (node (ref "IC3") (pin "34") (pinfunction "A9_34") (pintype "bidirectional"))
    )
    (net (code "33") (name "FMC_A10") (class "Default")
      (node (ref "IC1") (pin "56") (pinfunction "PG0_56") (pintype "bidirectional"))
      (node (ref "IC3") (pin "22") (pinfunction "A10_22") (pintype "bidirectional"))
    )
    (net (code "34") (name "FMC_A11") (class "Default")
      (node (ref "IC1") (pin "57") (pinfunction "PG1_57") (pintype "bidirectional"))
      (node (ref "IC3") (pin "35") (pinfunction "A11_35") (pintype "bidirectional"))
    )
    (net (code "35") (name "FMC_BA0") (class "Default")
      (node (ref "IC1") (pin "89") (pinfunction "PG4_89") (pintype "bidirectional"))
      (node (ref "IC3") (pin "20") (pinfunction "BA0_20") (pintype "bidirectional"))
    )
    (net (code "36") (name "FMC_BA1") (class "Default")
      (node (ref "IC1") (pin "90") (pinfunction "PG5_90") (pintype "bidirectional"))
      (node (ref "IC3") (pin "21") (pinfunction "BA1_21") (pintype "bidirectional"))
    )
    (net (code "37") (name "FMC_D0") (class "Default")
      (node (ref "IC1") (pin "85") (pinfunction "PD14_85") (pintype "bidirectional"))
      (node (ref "IC3") (pin "2") (pinfunction "DQ0_2") (pintype "bidirectional"))
    )
    (net (code "38") (name "FMC_D1") (class "Default")
      (node (ref "IC1") (pin "86") (pinfunction "PD15_86") (pintype "bidirectional"))
      (node (ref "IC3") (pin "4") (pinfunction "NC_1_4") (pintype "bidirectional"))
    )
    (net (code "39") (name "FMC_D2") (class "Default")
      (node (ref "IC1") (pin "114") (pinfunction "PD0_114") (pintype "bidirectional"))
      (node (ref "IC3") (pin "5") (pinfunction "DQ1_5") (pintype "bidirectional"))
    )
    (net (code "40") (name "FMC_D3") (class "Default")
      (node (ref "IC1") (pin "115") (pinfunction "PD1_115") (pintype "bidirectional"))
      (node (ref "IC3") (pin "7") (pinfunction "NC_2_7") (pintype "bidirectional"))
    )
    (net (code "41") (name "FMC_D4") (class "Default")
      (node (ref "IC1") (pin "58") (pinfunction "PE7_58") (pintype "bidirectional"))
      (node (ref "IC3") (pin "8") (pinfunction "DQ2_8") (pintype "bidirectional"))
    )
    (net (code "42") (name "FMC_D5") (class "Default")
      (node (ref "IC1") (pin "59") (pinfunction "PE8_59") (pintype "bidirectional"))
      (node (ref "IC3") (pin "10") (pinfunction "NC_3_10") (pintype "bidirectional"))
    )
    (net (code "43") (name "FMC_D6") (class "Default")
      (node (ref "IC1") (pin "60") (pinfunction "PE9_60") (pintype "bidirectional"))
      (node (ref "IC3") (pin "11") (pinfunction "DQ3_11") (pintype "bidirectional"))
    )
    (net (code "44") (name "FMC_D7") (class "Default")
      (node (ref "IC1") (pin "63") (pinfunction "PE10_63") (pintype "bidirectional"))
      (node (ref "IC3") (pin "13") (pinfunction "NC_4_13") (pintype "bidirectional"))
    )
    (net (code "45") (name "FMC_D8") (class "Default")
      (node (ref "IC1") (pin "64") (pinfunction "PE11_64") (pintype "bidirectional"))
      (node (ref "IC3") (pin "42") (pinfunction "NC_8_42") (pintype "bidirectional"))
    )
    (net (code "46") (name "FMC_D9") (class "Default")
      (node (ref "IC1") (pin "65") (pinfunction "PE12_65") (pintype "bidirectional"))
      (node (ref "IC3") (pin "44") (pinfunction "DQ4_44") (pintype "bidirectional"))
    )
    (net (code "47") (name "FMC_D10") (class "Default")
      (node (ref "IC1") (pin "66") (pinfunction "PE13_66") (pintype "bidirectional"))
      (node (ref "IC3") (pin "45") (pinfunction "NC_9_45") (pintype "bidirectional"))
    )
    (net (code "48") (name "FMC_D11") (class "Default")
      (node (ref "IC1") (pin "67") (pinfunction "PE14_67") (pintype "bidirectional"))
      (node (ref "IC3") (pin "47") (pinfunction "DQ5_47") (pintype "bidirectional"))
    )
    (net (code "49") (name "FMC_D12") (class "Default")
      (node (ref "IC1") (pin "68") (pinfunction "PE15_68") (pintype "bidirectional"))
      (node (ref "IC3") (pin "48") (pinfunction "NC_10_48") (pintype "bidirectional"))
    )
    (net (code "50") (name "FMC_D13") (class "Default")
      (node (ref "IC1") (pin "77") (pinfunction "PD8_77") (pintype "bidirectional"))
      (node (ref "IC3") (pin "50") (pinfunction "DQ6_50") (pintype "bidirectional"))
    )
    (net (code "51") (name "FMC_D14") (class "Default")
      (node (ref "IC1") (pin "78") (pinfunction "PD9_78") (pintype "bidirectional"))
      (node (ref "IC3") (pin "51") (pinfunction "NC_11_51") (pintype "bidirectional"))
    )
    (net (code "52") (name "FMC_D15") (class "Default")
      (node (ref "IC1") (pin "79") (pinfunction "PD10_79") (pintype "bidirectional"))
      (node (ref "IC3") (pin "53") (pinfunction "DQ7_53") (pintype "bidirectional"))
    )
    (net (code "53") (name "FMC_NBL0") (class "Default")
      (node (ref "IC1") (pin "141") (pinfunction "PE0_141") (pintype "bidirectional"))
      (node (ref "IC3") (pin "15") (pinfunction "NC_5_15") (pintype "bidirectional"))
    )
    (net (code "54") (name "FMC_NBL1") (class "Default")
      (node (ref "IC1") (pin "142") (pinfunction "PE1_142") (pintype "bidirectional"))
      (node (ref "IC3") (pin "39") (pinfunction "DQM_39") (pintype "bidirectional"))
    )
    (net (code "55") (name "FMC_SDCKE0") (class "Default")
      (node (ref "IC1") (pin "45") (pinfunction "PC5_45") (pintype "bidirectional"))
      (node (ref "IC3") (pin "37") (pinfunction "CKE_37") (pintype "bidirectional"))
    )
    (net (code "56") (name "FMC_SDCLK") (class "Default")
      (node (ref "IC1") (pin "93") (pinfunction "PG8_93") (pintype "bidirectional"))
      (node (ref "IC3") (pin "38") (pinfunction "CLK_38") (pintype "bidirectional"))
    )
    (net (code "57") (name "FMC_SDNCAS") (class "Default")
      (node (ref "IC1") (pin "132") (pinfunction "PG15_132") (pintype "bidirectional"))
      (node (ref "IC3") (pin "17") (pinfunction "~{CAS}_17") (pintype "bidirectional"))
    )
    (net (code "58") (name "FMC_SDNE0") (class "Default")
      (node (ref "IC1") (pin "44") (pinfunction "PC4_44") (pintype "bidirectional"))
      (node (ref "IC3") (pin "19") (pinfunction "~{CS}_19") (pintype "bidirectional"))
    )
    (net (code "59") (name "FMC_SDNRAS") (class "Default")
      (node (ref "IC1") (pin "49") (pinfunction "PF11_49") (pintype "bidirectional"))
      (node (ref "IC3") (pin "18") (pinfunction "~{RAS}_18") (pintype "bidirectional"))
    )
    (net (code "60") (name "FMC_SDNWE") (class "Default")
      (node (ref "IC1") (pin "26") (pinfunction "PC0_26") (pintype "bidirectional"))
      (node (ref "IC3") (pin "16") (pinfunction "~{WE}_16") (pintype "bidirectional"))
    )
    (net (code "61") (name "GND") (class "Default")
      (node (ref "C1") (pin "P$1") (pinfunction "1_P$1") (pintype "passive"))
      (node (ref "C10") (pin "P$1") (pinfunction "1_P$1") (pintype "passive"))
      (node (ref "C11") (pin "P$1") (pinfunction "1_P$1") (pintype "passive"))
      (node (ref "C12") (pin "P$1") (pinfunction "1_P$1") (pintype "passive"))
      (node (ref "C13") (pin "P$1") (pinfunction "1_P$1") (pintype "passive"))
      (node (ref "C14") (pin "P$1") (pinfunction "1_P$1") (pintype "passive"))
      (node (ref "C15") (pin "P$1") (pinfunction "1_P$1") (pintype "passive"))
      (node (ref "C16") (pin "P$1") (pinfunction "1_P$1") (pintype "passive"))
      (node (ref "C17") (pin "P$1") (pinfunction "1_P$1") (pintype "passive"))
      (node (ref "C18") (pin "P$1") (pinfunction "1_P$1") (pintype "passive"))
      (node (ref "C19") (pin "P$1") (pinfunction "1_P$1") (pintype "passive"))
      (node (ref "C2") (pin "P$1") (pinfunction "1_P$1") (pintype "passive"))
      (node (ref "C20") (pin "P$1") (pinfunction "1_P$1") (pintype "passive"))
      (node (ref "C21") (pin "P$2") (pinfunction "2_P$2") (pintype "passive"))
      (node (ref "C22") (pin "P$2") (pinfunction "2_P$2") (pintype "passive"))
      (node (ref "C23") (pin "P$2") (pinfunction "2_P$2") (pintype "passive"))
      (node (ref "C24") (pin "P$2") (pinfunction "2_P$2") (pintype "passive"))
      (node (ref "C25") (pin "P$2") (pinfunction "2_P$2") (pintype "passive"))
      (node (ref "C26") (pin "P$2") (pinfunction "2_P$2") (pintype "passive"))
      (node (ref "C27") (pin "P$2") (pinfunction "2_P$2") (pintype "passive"))
      (node (ref "C28") (pin "P$2") (pinfunction "2_P$2") (pintype "passive"))
      (node (ref "C29") (pin "P$2") (pinfunction "2_P$2") (pintype "passive"))
      (node (ref "C3") (pin "P$1") (pinfunction "1_P$1") (pintype "passive"))
      (node (ref "C30") (pin "P$2") (pinfunction "2_P$2") (pintype "passive"))
      (node (ref "C31") (pin "P$2") (pinfunction "2_P$2") (pintype "passive"))
      (node (ref "C32") (pin "P$2") (pinfunction "2_P$2") (pintype "passive"))
      (node (ref "C35") (pin "P$1") (pinfunction "1_P$1") (pintype "passive"))
      (node (ref "C38") (pin "P$1") (pinfunction "1_P$1") (pintype "passive"))
      (node (ref "C4") (pin "P$1") (pinfunction "1_P$1") (pintype "passive"))
      (node (ref "C45") (pin "P$1") (pinfunction "1_P$1") (pintype "passive"))
      (node (ref "C46") (pin "P$2") (pinfunction "2_P$2") (pintype "passive"))
      (node (ref "C47") (pin "P$2") (pinfunction "2_P$2") (pintype "passive"))
      (node (ref "C5") (pin "P$1") (pinfunction "1_P$1") (pintype "passive"))
      (node (ref "C6") (pin "P$1") (pinfunction "1_P$1") (pintype "passive"))
      (node (ref "C7") (pin "P$1") (pinfunction "1_P$1") (pintype "passive"))
      (node (ref "C8") (pin "P$1") (pinfunction "1_P$1") (pintype "passive"))
      (node (ref "C9") (pin "P$1") (pinfunction "1_P$1") (pintype "passive"))
      (node (ref "CP1") (pin "P$2") (pinfunction "-_P$2") (pintype "passive"))
      (node (ref "CP2") (pin "P$2") (pinfunction "-_P$2") (pintype "passive"))
      (node (ref "FB01") (pin "P$2") (pinfunction "2_P$2") (pintype "passive"))
      (node (ref "FB03") (pin "P$2") (pinfunction "2_P$2") (pintype "passive"))
      (node (ref "IC1") (pin "107") (pinfunction "VSS_7_107") (pintype "bidirectional"))
      (node (ref "IC1") (pin "120") (pinfunction "VSS_8_120") (pintype "bidirectional"))
      (node (ref "IC1") (pin "130") (pinfunction "VSS_9_130") (pintype "bidirectional"))
      (node (ref "IC1") (pin "16") (pinfunction "VSS_1_16") (pintype "bidirectional"))
      (node (ref "IC1") (pin "31") (pinfunction "VSSA_31") (pintype "bidirectional"))
      (node (ref "IC1") (pin "38") (pinfunction "VSS_2_38") (pintype "bidirectional"))
      (node (ref "IC1") (pin "51") (pinfunction "VSS_3_51") (pintype "bidirectional"))
      (node (ref "IC1") (pin "61") (pinfunction "VSS_4_61") (pintype "bidirectional"))
      (node (ref "IC1") (pin "83") (pinfunction "VSS_5_83") (pintype "bidirectional"))
      (node (ref "IC1") (pin "94") (pinfunction "VSS_6_94") (pintype "bidirectional"))
      (node (ref "IC2") (pin "2") (pinfunction "GND_2") (pintype "bidirectional"))
      (node (ref "IC3") (pin "12") (pinfunction "VSSQ_2_12") (pintype "bidirectional"))
      (node (ref "IC3") (pin "28") (pinfunction "VSS_1_28") (pintype "bidirectional"))
      (node (ref "IC3") (pin "41") (pinfunction "VSS_2_41") (pintype "bidirectional"))
      (node (ref "IC3") (pin "46") (pinfunction "VSSQ_3_46") (pintype "bidirectional"))
      (node (ref "IC3") (pin "52") (pinfunction "VSSQ_4_52") (pintype "bidirectional"))
      (node (ref "IC3") (pin "54") (pinfunction "VSS_3_54") (pintype "bidirectional"))
      (node (ref "IC3") (pin "6") (pinfunction "VSSQ_1_6") (pintype "bidirectional"))
      (node (ref "IC7") (pin "2") (pinfunction "GND_2") (pintype "bidirectional"))
      (node (ref "IC8") (pin "5") (pinfunction "GND_5") (pintype "bidirectional"))
      (node (ref "J1") (pin "13") (pinfunction "13_13") (pintype "bidirectional"))
      (node (ref "J1") (pin "14") (pinfunction "14_14") (pintype "bidirectional"))
      (node (ref "J1") (pin "15") (pinfunction "15_15") (pintype "bidirectional"))
      (node (ref "J1") (pin "16") (pinfunction "16_16") (pintype "bidirectional"))
      (node (ref "J1") (pin "17") (pinfunction "17_17") (pintype "bidirectional"))
      (node (ref "J1") (pin "18") (pinfunction "18_18") (pintype "bidirectional"))
      (node (ref "J1") (pin "19") (pinfunction "19_19") (pintype "bidirectional"))
      (node (ref "J1") (pin "20") (pinfunction "20_20") (pintype "bidirectional"))
      (node (ref "J1") (pin "3") (pinfunction "3_3") (pintype "bidirectional"))
      (node (ref "J1") (pin "37") (pinfunction "37_37") (pintype "bidirectional"))
      (node (ref "J1") (pin "38") (pinfunction "38_38") (pintype "bidirectional"))
      (node (ref "J1") (pin "39") (pinfunction "39_39") (pintype "bidirectional"))
      (node (ref "J1") (pin "4") (pinfunction "4_4") (pintype "bidirectional"))
      (node (ref "J1") (pin "40") (pinfunction "40_40") (pintype "bidirectional"))
      (node (ref "J1") (pin "41") (pinfunction "41_41") (pintype "bidirectional"))
      (node (ref "J1") (pin "42") (pinfunction "42_42") (pintype "bidirectional"))
      (node (ref "J1") (pin "43") (pinfunction "43_43") (pintype "bidirectional"))
      (node (ref "J1") (pin "44") (pinfunction "44_44") (pintype "bidirectional"))
      (node (ref "J1") (pin "45") (pinfunction "45_45") (pintype "bidirectional"))
      (node (ref "J1") (pin "46") (pinfunction "46_46") (pintype "bidirectional"))
      (node (ref "J1") (pin "47") (pinfunction "47_47") (pintype "bidirectional"))
      (node (ref "J1") (pin "48") (pinfunction "48_48") (pintype "bidirectional"))
      (node (ref "J1") (pin "49") (pinfunction "49_49") (pintype "bidirectional"))
      (node (ref "J1") (pin "7") (pinfunction "7_7") (pintype "bidirectional"))
      (node (ref "J2") (pin "6") (pinfunction "6_6") (pintype "bidirectional"))
      (node (ref "J4") (pin "17") (pinfunction "17_17") (pintype "bidirectional"))
      (node (ref "J4") (pin "18") (pinfunction "18_18") (pintype "bidirectional"))
      (node (ref "J7") (pin "P$3") (pinfunction "P$3_P$3") (pintype "bidirectional"))
      (node (ref "LED1") (pin "1") (pinfunction "K_1") (pintype "bidirectional"))
      (node (ref "LED2") (pin "1") (pinfunction "K_1") (pintype "bidirectional"))
      (node (ref "LED3") (pin "1") (pinfunction "K_1") (pintype "bidirectional"))
      (node (ref "R10") (pin "P$2") (pinfunction "2_P$2") (pintype "passive"))
      (node (ref "R11") (pin "P$1") (pinfunction "1_P$1") (pintype "passive"))
      (node (ref "R25") (pin "P$1") (pinfunction "1_P$1") (pintype "passive"))
      (node (ref "R26") (pin "P$1") (pinfunction "1_P$1") (pintype "passive"))
      (node (ref "R3") (pin "P$1") (pinfunction "1_P$1") (pintype "passive"))
      (node (ref "S1") (pin "3") (pinfunction "3_3") (pintype "passive"))
      (node (ref "S1") (pin "4") (pinfunction "4_4") (pintype "passive"))
      (node (ref "S2") (pin "3") (pinfunction "3_3") (pintype "passive"))
      (node (ref "S2") (pin "4") (pinfunction "4_4") (pintype "passive"))
      (node (ref "USB1") (pin "A1") (pinfunction "GND_1_A1") (pintype "bidirectional"))
      (node (ref "USB1") (pin "A12") (pinfunction "GND_2_A12") (pintype "bidirectional"))
    )
    (net (code "62") (name "HPHONE_L") (class "Default")
      (node (ref "IC4") (pin "6") (pinfunction "HP_L_6") (pintype "bidirectional"))
      (node (ref "R21") (pin "P$1") (pinfunction "1_P$1") (pintype "passive"))
    )
    (net (code "63") (name "HPHONE_R") (class "Default")
      (node (ref "IC4") (pin "2") (pinfunction "HP_R_2") (pintype "bidirectional"))
      (node (ref "R20") (pin "P$1") (pinfunction "1_P$1") (pintype "passive"))
    )
    (net (code "64") (name "HPHONE_VGND") (class "Default")
      (node (ref "IC4") (pin "4") (pinfunction "HP_VGND_4") (pintype "bidirectional"))
      (node (ref "J3") (pin "1") (pinfunction "SLEEVE_1") (pintype "bidirectional"))
    )
    (net (code "65") (name "HP_L") (class "Default")
      (node (ref "J3") (pin "2") (pinfunction "TIP_2") (pintype "bidirectional"))
      (node (ref "R21") (pin "P$2") (pinfunction "2_P$2") (pintype "passive"))
    )
    (net (code "66") (name "HP_R") (class "Default")
      (node (ref "J3") (pin "3") (pinfunction "RING_3") (pintype "bidirectional"))
      (node (ref "R20") (pin "P$2") (pinfunction "2_P$2") (pintype "passive"))
    )
    (net (code "67") (name "I2C3_SCL") (class "Default")
      (node (ref "IC1") (pin "100") (pinfunction "PA8_100") (pintype "bidirectional"))
      (node (ref "IC4") (pin "29") (pinfunction "CTRL_CLK_29") (pintype "bidirectional"))
      (node (ref "R18") (pin "P$2") (pinfunction "2_P$2") (pintype "passive"))
    )
    (net (code "68") (name "I2C3_SDA") (class "Default")
      (node (ref "IC1") (pin "99") (pinfunction "PC9_99") (pintype "bidirectional"))
      (node (ref "IC4") (pin "27") (pinfunction "CTRL_DATA_27") (pintype "bidirectional"))
      (node (ref "R19") (pin "P$2") (pinfunction "2_P$2") (pintype "passive"))
    )
    (net (code "69") (name "I2S3_CK") (class "Default")
      (node (ref "IC1") (pin "111") (pinfunction "PC10_111") (pintype "bidirectional"))
      (node (ref "IC4") (pin "24") (pinfunction "I2S_SCLK_24") (pintype "bidirectional"))
    )
    (net (code "70") (name "I2S3_MCK") (class "Default")
      (node (ref "IC1") (pin "97") (pinfunction "PC7_97") (pintype "bidirectional"))
      (node (ref "R22") (pin "P$2") (pinfunction "2_P$2") (pintype "passive"))
    )
    (net (code "71") (name "I2S3_MCK_IN") (class "Default")
      (node (ref "IC4") (pin "21") (pinfunction "SYS_MCLK_21") (pintype "bidirectional"))
      (node (ref "R22") (pin "P$1") (pinfunction "1_P$1") (pintype "passive"))
    )
    (net (code "72") (name "I2S3_SDI") (class "Default")
      (node (ref "IC1") (pin "112") (pinfunction "PC11_112") (pintype "bidirectional"))
      (node (ref "IC4") (pin "25") (pinfunction "I2S_DOUT_25") (pintype "bidirectional"))
    )
    (net (code "73") (name "I2S3_SDO") (class "Default")
      (node (ref "IC1") (pin "113") (pinfunction "PC12_113") (pintype "bidirectional"))
      (node (ref "IC4") (pin "26") (pinfunction "I2S_DIN_26") (pintype "bidirectional"))
    )
    (net (code "74") (name "I2S3_WS") (class "Default")
      (node (ref "IC1") (pin "40") (pinfunction "PA4_40") (pintype "bidirectional"))
      (node (ref "IC4") (pin "23") (pinfunction "I2S_LRCLK_23") (pintype "bidirectional"))
    )
    (net (code "75") (name "LCD_BL") (class "Default")
      (node (ref "IC1") (pin "129") (pinfunction "PG14_129") (pintype "bidirectional"))
      (node (ref "R9") (pin "P$2") (pinfunction "2_P$2") (pintype "passive"))
    )
    (net (code "76") (name "LCD_CS") (class "Default")
      (node (ref "IC1") (pin "116") (pinfunction "PD2_116") (pintype "bidirectional"))
      (node (ref "J1") (pin "11") (pinfunction "11_11") (pintype "bidirectional"))
    )
    (net (code "77") (name "LCD_D0") (class "Default")
      (node (ref "IC1") (pin "46") (pinfunction "PB0_46") (pintype "bidirectional"))
      (node (ref "J1") (pin "36") (pinfunction "36_36") (pintype "bidirectional"))
    )
    (net (code "78") (name "LCD_D1") (class "Default")
      (node (ref "IC1") (pin "47") (pinfunction "PB1_47") (pintype "bidirectional"))
      (node (ref "J1") (pin "35") (pinfunction "35_35") (pintype "bidirectional"))
    )
    (net (code "79") (name "LCD_D2") (class "Default")
      (node (ref "IC1") (pin "48") (pinfunction "PB2_48") (pintype "bidirectional"))
      (node (ref "J1") (pin "34") (pinfunction "34_34") (pintype "bidirectional"))
    )
    (net (code "80") (name "LCD_D3") (class "Default")
      (node (ref "IC1") (pin "133") (pinfunction "PB3_133") (pintype "bidirectional"))
      (node (ref "J1") (pin "33") (pinfunction "33_33") (pintype "bidirectional"))
    )
    (net (code "81") (name "LCD_D4") (class "Default")
      (node (ref "IC1") (pin "134") (pinfunction "PB4_134") (pintype "bidirectional"))
      (node (ref "J1") (pin "32") (pinfunction "32_32") (pintype "bidirectional"))
    )
    (net (code "82") (name "LCD_D5") (class "Default")
      (node (ref "IC1") (pin "135") (pinfunction "PB5_135") (pintype "bidirectional"))
      (node (ref "J1") (pin "31") (pinfunction "31_31") (pintype "bidirectional"))
    )
    (net (code "83") (name "LCD_D6") (class "Default")
      (node (ref "IC1") (pin "136") (pinfunction "PB6_136") (pintype "bidirectional"))
      (node (ref "J1") (pin "30") (pinfunction "30_30") (pintype "bidirectional"))
    )
    (net (code "84") (name "LCD_D7") (class "Default")
      (node (ref "IC1") (pin "137") (pinfunction "PB7_137") (pintype "bidirectional"))
      (node (ref "J1") (pin "29") (pinfunction "29_29") (pintype "bidirectional"))
    )
    (net (code "85") (name "LCD_D8") (class "Default")
      (node (ref "IC1") (pin "139") (pinfunction "PB8_139") (pintype "bidirectional"))
      (node (ref "J1") (pin "28") (pinfunction "28_28") (pintype "bidirectional"))
    )
    (net (code "86") (name "LCD_D9") (class "Default")
      (node (ref "IC1") (pin "140") (pinfunction "PB9_140") (pintype "bidirectional"))
      (node (ref "J1") (pin "27") (pinfunction "27_27") (pintype "bidirectional"))
    )
    (net (code "87") (name "LCD_D10") (class "Default")
      (node (ref "IC1") (pin "69") (pinfunction "PB10_69") (pintype "bidirectional"))
      (node (ref "J1") (pin "26") (pinfunction "26_26") (pintype "bidirectional"))
    )
    (net (code "88") (name "LCD_D11") (class "Default")
      (node (ref "IC1") (pin "70") (pinfunction "PB11_70") (pintype "bidirectional"))
      (node (ref "J1") (pin "25") (pinfunction "25_25") (pintype "bidirectional"))
    )
    (net (code "89") (name "LCD_D12") (class "Default")
      (node (ref "IC1") (pin "73") (pinfunction "PB12_73") (pintype "bidirectional"))
      (node (ref "J1") (pin "24") (pinfunction "24_24") (pintype "bidirectional"))
    )
    (net (code "90") (name "LCD_D13") (class "Default")
      (node (ref "IC1") (pin "74") (pinfunction "PB13_74") (pintype "bidirectional"))
      (node (ref "J1") (pin "23") (pinfunction "23_23") (pintype "bidirectional"))
    )
    (net (code "91") (name "LCD_D14") (class "Default")
      (node (ref "IC1") (pin "75") (pinfunction "PB14_75") (pintype "bidirectional"))
      (node (ref "J1") (pin "22") (pinfunction "22_22") (pintype "bidirectional"))
    )
    (net (code "92") (name "LCD_D15") (class "Default")
      (node (ref "IC1") (pin "76") (pinfunction "PB15_76") (pintype "bidirectional"))
      (node (ref "J1") (pin "21") (pinfunction "21_21") (pintype "bidirectional"))
    )
    (net (code "93") (name "LCD_RD") (class "Default")
      (node (ref "IC1") (pin "117") (pinfunction "PD3_117") (pintype "bidirectional"))
      (node (ref "J1") (pin "10") (pinfunction "10_10") (pintype "bidirectional"))
    )
    (net (code "94") (name "LCD_RESET") (class "Default")
      (node (ref "IC1") (pin "128") (pinfunction "PG13_128") (pintype "bidirectional"))
      (node (ref "J1") (pin "12") (pinfunction "12_12") (pintype "bidirectional"))
    )
    (net (code "95") (name "LCD_RS") (class "Default")
      (node (ref "IC1") (pin "119") (pinfunction "PD5_119") (pintype "bidirectional"))
      (node (ref "J1") (pin "8") (pinfunction "8_8") (pintype "bidirectional"))
    )
    (net (code "96") (name "LCD_WR") (class "Default")
      (node (ref "IC1") (pin "118") (pinfunction "PD4_118") (pintype "bidirectional"))
      (node (ref "J1") (pin "9") (pinfunction "9_9") (pintype "bidirectional"))
    )
    (net (code "97") (name "LED0") (class "Default")
      (node (ref "IC1") (pin "80") (pinfunction "PD11_80") (pintype "bidirectional"))
      (node (ref "R5") (pin "P$2") (pinfunction "2_P$2") (pintype "passive"))
    )
    (net (code "98") (name "LED1") (class "Default")
      (node (ref "IC1") (pin "81") (pinfunction "PD12_81") (pintype "bidirectional"))
      (node (ref "R6") (pin "P$2") (pinfunction "2_P$2") (pintype "passive"))
    )
    (net (code "99") (name "LED2") (class "Default")
      (node (ref "IC1") (pin "82") (pinfunction "PD13_82") (pintype "bidirectional"))
      (node (ref "R7") (pin "P$2") (pinfunction "2_P$2") (pintype "passive"))
    )
    (net (code "100") (name "LINEIN_L") (class "Default")
      (node (ref "IC4") (pin "14") (pinfunction "LINEN_L_14") (pintype "bidirectional"))
    )
    (net (code "101") (name "LINEIN_R") (class "Default")
      (node (ref "IC4") (pin "13") (pinfunction "LINEN_R_13") (pintype "bidirectional"))
    )
    (net (code "102") (name "LINEOUT_L") (class "Default")
      (node (ref "IC4") (pin "12") (pinfunction "LINEOUT_L_12") (pintype "bidirectional"))
    )
    (net (code "103") (name "LINEOUT_R") (class "Default")
      (node (ref "IC4") (pin "11") (pinfunction "LINEOUT_R_11") (pintype "bidirectional"))
    )
    (net (code "104") (name "MIC") (class "Default")
      (node (ref "C34") (pin "P$2") (pinfunction "2_P$2") (pintype "passive"))
      (node (ref "IC4") (pin "15") (pinfunction "MIC_15") (pintype "bidirectional"))
    )
    (net (code "105") (name "MIDI_RX") (class "Default")
      (node (ref "IC1") (pin "101") (pinfunction "PA9_101") (pintype "bidirectional"))
      (node (ref "IC8") (pin "4") (pinfunction "VO_4") (pintype "bidirectional"))
      (node (ref "R29") (pin "P$2") (pinfunction "2_P$2") (pintype "passive"))
    )
    (net (code "106") (name "MIDI_RX_A") (class "Default")
      (node (ref "D2") (pin "C") (pinfunction "C_C") (pintype "passive"))
      (node (ref "IC8") (pin "1") (pinfunction "ANODE_1") (pintype "bidirectional"))
      (node (ref "R28") (pin "P$2") (pinfunction "2_P$2") (pintype "passive"))
    )
    (net (code "107") (name "MIDI_RX_C") (class "Default")
      (node (ref "D2") (pin "A") (pinfunction "A_A") (pintype "passive"))
      (node (ref "IC8") (pin "2") (pinfunction "CATHODE_2") (pintype "bidirectional"))
      (node (ref "J9") (pin "2") (pinfunction "TIP_2") (pintype "bidirectional"))
    )
    (net (code "108") (name "MIDI_RX_GND") (class "Default")
      (node (ref "J9") (pin "1") (pinfunction "SLEEVE_1") (pintype "bidirectional"))
      (node (ref "R26") (pin "P$2") (pinfunction "2_P$2") (pintype "passive"))
    )
    (net (code "109") (name "MIDI_RX_SOURCE") (class "Default")
      (node (ref "J9") (pin "3") (pinfunction "RING_3") (pintype "bidirectional"))
      (node (ref "R28") (pin "P$1") (pinfunction "1_P$1") (pintype "passive"))
    )
    (net (code "110") (name "MIDI_TX") (class "Default")
      (node (ref "IC1") (pin "96") (pinfunction "PC6_96") (pintype "bidirectional"))
      (node (ref "R24") (pin "P$2") (pinfunction "2_P$2") (pintype "passive"))
    )
    (net (code "111") (name "MIDI_TX_GND") (class "Default")
      (node (ref "J8") (pin "1") (pinfunction "SLEEVE_1") (pintype "bidirectional"))
      (node (ref "R25") (pin "P$2") (pinfunction "2_P$2") (pintype "passive"))
    )
    (net (code "112") (name "MIDI_TX_SINK") (class "Default")
      (node (ref "J8") (pin "2") (pinfunction "TIP_2") (pintype "bidirectional"))
      (node (ref "R24") (pin "P$1") (pinfunction "1_P$1") (pintype "passive"))
    )
    (net (code "113") (name "MIDI_TX_SOURCE") (class "Default")
      (node (ref "J8") (pin "3") (pinfunction "RING_3") (pintype "bidirectional"))
      (node (ref "R27") (pin "P$2") (pinfunction "2_P$2") (pintype "passive"))
    )
    (net (code "114") (name "NRST") (class "Default")
      (node (ref "IC1") (pin "25") (pinfunction "NRST_25") (pintype "bidirectional"))
      (node (ref "J7") (pin "P$1") (pinfunction "P$1_P$1") (pintype "bidirectional"))
      (node (ref "R1") (pin "P$1") (pinfunction "1_P$1") (pintype "passive"))
    )
    (net (code "115") (name "Net-(C4-2)") (class "Default")
      (node (ref "C4") (pin "P$2") (pinfunction "2_P$2") (pintype "passive"))
      (node (ref "R1") (pin "P$2") (pinfunction "2_P$2") (pintype "passive"))
      (node (ref "R4") (pin "P$1") (pinfunction "1_P$1") (pintype "passive"))
      (node (ref "S1") (pin "1") (pinfunction "1_1") (pintype "passive"))
      (node (ref "S1") (pin "2") (pinfunction "2_2") (pintype "passive"))
    )
    (net (code "116") (name "Net-(C45-2)") (class "Default")
      (node (ref "C45") (pin "P$2") (pinfunction "2_P$2") (pintype "passive"))
      (node (ref "R15") (pin "P$2") (pinfunction "2_P$2") (pintype "passive"))
      (node (ref "R23") (pin "P$1") (pinfunction "1_P$1") (pintype "passive"))
      (node (ref "S2") (pin "1") (pinfunction "1_1") (pintype "passive"))
      (node (ref "S2") (pin "2") (pinfunction "2_2") (pintype "passive"))
    )
    (net (code "117") (name "Net-(LED1-A)") (class "Default")
      (node (ref "LED1") (pin "2") (pinfunction "A_2") (pintype "bidirectional"))
      (node (ref "R5") (pin "P$1") (pinfunction "1_P$1") (pintype "passive"))
    )
    (net (code "118") (name "Net-(LED2-A)") (class "Default")
      (node (ref "LED2") (pin "2") (pinfunction "A_2") (pintype "bidirectional"))
      (node (ref "R6") (pin "P$1") (pinfunction "1_P$1") (pintype "passive"))
    )
    (net (code "119") (name "Net-(LED3-A)") (class "Default")
      (node (ref "LED3") (pin "2") (pinfunction "A_2") (pintype "bidirectional"))
      (node (ref "R7") (pin "P$1") (pinfunction "1_P$1") (pintype "passive"))
    )
    (net (code "120") (name "PDR_ON") (class "Default")
      (node (ref "IC1") (pin "143") (pinfunction "PDR_ON_143") (pintype "bidirectional"))
      (node (ref "R2") (pin "P$2") (pinfunction "2_P$2") (pintype "passive"))
    )
    (net (code "121") (name "PH0") (class "Default")
      (node (ref "C8") (pin "P$2") (pinfunction "2_P$2") (pintype "passive"))
      (node (ref "IC1") (pin "23") (pinfunction "PH0-OSC_IN_23") (pintype "bidirectional"))
      (node (ref "Y1") (pin "1") (pinfunction "X1_1") (pintype "bidirectional"))
    )
    (net (code "122") (name "PH1") (class "Default")
      (node (ref "C10") (pin "P$2") (pinfunction "2_P$2") (pintype "passive"))
      (node (ref "IC1") (pin "24") (pinfunction "PH1-OSC_OUT_24") (pintype "bidirectional"))
      (node (ref "Y1") (pin "2") (pinfunction "X2_2") (pintype "bidirectional"))
    )
    (net (code "123") (name "SDMMC2_CK") (class "Default")
      (node (ref "IC1") (pin "122") (pinfunction "PD6_122") (pintype "bidirectional"))
      (node (ref "J2") (pin "5") (pinfunction "5_5") (pintype "bidirectional"))
    )
    (net (code "124") (name "SDMMC2_CMD") (class "Default")
      (node (ref "IC1") (pin "123") (pinfunction "PD7_123") (pintype "bidirectional"))
      (node (ref "J2") (pin "3") (pinfunction "3_3") (pintype "bidirectional"))
      (node (ref "R14") (pin "P$2") (pinfunction "2_P$2") (pintype "passive"))
    )
    (net (code "125") (name "SDMMC2_D0") (class "Default")
      (node (ref "IC1") (pin "124") (pinfunction "PG9_124") (pintype "bidirectional"))
      (node (ref "J2") (pin "7") (pinfunction "7_7") (pintype "bidirectional"))
      (node (ref "R12") (pin "P$2") (pinfunction "2_P$2") (pintype "passive"))
    )
    (net (code "126") (name "SDMMC2_D1") (class "Default")
      (node (ref "IC1") (pin "125") (pinfunction "PG10_125") (pintype "bidirectional"))
      (node (ref "J2") (pin "8") (pinfunction "8_8") (pintype "bidirectional"))
      (node (ref "R16") (pin "P$2") (pinfunction "2_P$2") (pintype "passive"))
    )
    (net (code "127") (name "SDMMC2_D2") (class "Default")
      (node (ref "IC1") (pin "126") (pinfunction "PG11_126") (pintype "bidirectional"))
      (node (ref "J2") (pin "1") (pinfunction "1_1") (pintype "bidirectional"))
      (node (ref "R13") (pin "P$2") (pinfunction "2_P$2") (pintype "passive"))
    )
    (net (code "128") (name "SDMMC2_D3") (class "Default")
      (node (ref "IC1") (pin "127") (pinfunction "PG12_127") (pintype "bidirectional"))
      (node (ref "J2") (pin "2") (pinfunction "2_2") (pintype "bidirectional"))
      (node (ref "R17") (pin "P$2") (pinfunction "2_P$2") (pintype "passive"))
    )
    (net (code "129") (name "SDMMC2_DETECT") (class "Default")
      (node (ref "IC1") (pin "7") (pinfunction "PC13_7") (pintype "bidirectional"))
      (node (ref "J2") (pin "9") (pinfunction "9_9") (pintype "bidirectional"))
    )
    (net (code "130") (name "SD_GND") (class "Default")
      (node (ref "FB03") (pin "P$1") (pinfunction "1_P$1") (pintype "passive"))
      (node (ref "J2") (pin "10") (pinfunction "G_1_10") (pintype "bidirectional"))
      (node (ref "J2") (pin "11") (pinfunction "G_2_11") (pintype "bidirectional"))
      (node (ref "J2") (pin "12") (pinfunction "G_3_12") (pintype "bidirectional"))
      (node (ref "J2") (pin "13") (pinfunction "G_4_13") (pintype "bidirectional"))
    )
    (net (code "131") (name "SWCLK") (class "Default")
      (node (ref "IC1") (pin "109") (pinfunction "PA14_109") (pintype "bidirectional"))
      (node (ref "J7") (pin "P$4") (pinfunction "P$4_P$4") (pintype "bidirectional"))
    )
    (net (code "132") (name "SWDIO") (class "Default")
      (node (ref "IC1") (pin "105") (pinfunction "PA13_105") (pintype "bidirectional"))
      (node (ref "J7") (pin "P$2") (pinfunction "P$2_P$2") (pintype "bidirectional"))
    )
    (net (code "133") (name "SYNC_IN") (class "Default")
      (node (ref "IC1") (pin "20") (pinfunction "PF8_20") (pintype "bidirectional"))
      (node (ref "J5") (pin "2") (pinfunction "TIP_2") (pintype "bidirectional"))
    )
    (net (code "134") (name "SYNC_IN_RX") (class "Default")
      (node (ref "IC1") (pin "18") (pinfunction "PF6_18") (pintype "bidirectional"))
      (node (ref "J5") (pin "3") (pinfunction "RING_3") (pintype "bidirectional"))
    )
    (net (code "135") (name "SYNC_IN_TX") (class "Default")
      (node (ref "IC1") (pin "19") (pinfunction "PF7_19") (pintype "bidirectional"))
      (node (ref "J5") (pin "1") (pinfunction "SLEEVE_1") (pintype "bidirectional"))
    )
    (net (code "136") (name "SYNC_OUT") (class "Default")
      (node (ref "IC1") (pin "102") (pinfunction "PA10_102") (pintype "bidirectional"))
      (node (ref "J6") (pin "2") (pinfunction "TIP_2") (pintype "bidirectional"))
    )
    (net (code "137") (name "SYNC_OUT_RX") (class "Default")
      (node (ref "IC1") (pin "103") (pinfunction "PA11_103") (pintype "bidirectional"))
      (node (ref "J6") (pin "1") (pinfunction "SLEEVE_1") (pintype "bidirectional"))
    )
    (net (code "138") (name "SYNC_OUT_TX") (class "Default")
      (node (ref "IC1") (pin "104") (pinfunction "PA12_104") (pintype "bidirectional"))
      (node (ref "J6") (pin "3") (pinfunction "RING_3") (pintype "bidirectional"))
    )
    (net (code "139") (name "VAG") (class "Default")
      (node (ref "C33") (pin "P$2") (pinfunction "2_P$2") (pintype "passive"))
      (node (ref "IC4") (pin "10") (pinfunction "VAG_10") (pintype "bidirectional"))
    )
    (net (code "140") (name "VCAP_1") (class "Default")
      (node (ref "C17") (pin "P$2") (pinfunction "2_P$2") (pintype "passive"))
      (node (ref "IC1") (pin "71") (pinfunction "VCAP_1_71") (pintype "bidirectional"))
    )
    (net (code "141") (name "VCAP_2") (class "Default")
      (node (ref "C18") (pin "P$2") (pinfunction "2_P$2") (pintype "passive"))
      (node (ref "IC1") (pin "106") (pinfunction "VCAP_2_106") (pintype "bidirectional"))
    )
    (net (code "142") (name "unconnected-(IC1-PA5-Pad41)") (class "Default")
      (node (ref "IC1") (pin "41") (pinfunction "PA5_41") (pintype "bidirectional"))
    )
    (net (code "143") (name "unconnected-(IC1-PA6-Pad42)") (class "Default")
      (node (ref "IC1") (pin "42") (pinfunction "PA6_42") (pintype "bidirectional"))
    )
    (net (code "144") (name "unconnected-(IC1-PA15-Pad110)") (class "Default")
      (node (ref "IC1") (pin "110") (pinfunction "PA15_110") (pintype "bidirectional"))
    )
    (net (code "145") (name "unconnected-(IC1-PC1-Pad27)") (class "Default")
      (node (ref "IC1") (pin "27") (pinfunction "PC1_27") (pintype "bidirectional"))
    )
    (net (code "146") (name "unconnected-(IC1-PC2_C-Pad28)") (class "Default")
      (node (ref "IC1") (pin "28") (pinfunction "PC2_C_28") (pintype "bidirectional"))
    )
    (net (code "147") (name "unconnected-(IC1-PC3_C-Pad29)") (class "Default")
      (node (ref "IC1") (pin "29") (pinfunction "PC3_C_29") (pintype "bidirectional"))
    )
    (net (code "148") (name "unconnected-(IC1-PC8-Pad98)") (class "Default")
      (node (ref "IC1") (pin "98") (pinfunction "PC8_98") (pintype "bidirectional"))
    )
    (net (code "149") (name "unconnected-(IC1-PC14-OSC32_IN-Pad8)") (class "Default")
      (node (ref "IC1") (pin "8") (pinfunction "PC14-OSC32_IN_8") (pintype "bidirectional"))
    )
    (net (code "150") (name "unconnected-(IC1-PC15-OSC32_OUT-Pad9)") (class "Default")
      (node (ref "IC1") (pin "9") (pinfunction "PC15-OSC32_OUT_9") (pintype "bidirectional"))
    )
    (net (code "151") (name "unconnected-(IC1-PE3-Pad2)") (class "Default")
      (node (ref "IC1") (pin "2") (pinfunction "PE3_2") (pintype "bidirectional"))
    )
    (net (code "152") (name "unconnected-(IC1-PF9-Pad21)") (class "Default")
      (node (ref "IC1") (pin "21") (pinfunction "PF9_21") (pintype "bidirectional"))
    )
    (net (code "153") (name "unconnected-(IC1-PG2-Pad87)") (class "Default")
      (node (ref "IC1") (pin "87") (pinfunction "PG2_87") (pintype "bidirectional"))
    )
    (net (code "154") (name "unconnected-(IC1-PG3-Pad88)") (class "Default")
      (node (ref "IC1") (pin "88") (pinfunction "PG3_88") (pintype "bidirectional"))
    )
    (net (code "155") (name "unconnected-(IC1-PG6-Pad91)") (class "Default")
      (node (ref "IC1") (pin "91") (pinfunction "PG6_91") (pintype "bidirectional"))
    )
    (net (code "156") (name "unconnected-(IC1-PG7-Pad92)") (class "Default")
      (node (ref "IC1") (pin "92") (pinfunction "PG7_92") (pintype "bidirectional"))
    )
    (net (code "157") (name "unconnected-(IC3-NC_6-Pad36)") (class "Default")
      (node (ref "IC3") (pin "36") (pinfunction "NC_6_36") (pintype "bidirectional"))
    )
    (net (code "158") (name "unconnected-(IC3-NC_7-Pad40)") (class "Default")
      (node (ref "IC3") (pin "40") (pinfunction "NC_7_40") (pintype "bidirectional"))
    )
    (net (code "159") (name "unconnected-(IC4-CPFILT-Pad18)") (class "Default")
      (node (ref "IC4") (pin "18") (pinfunction "CPFILT_18") (pintype "bidirectional"))
    )
    (net (code "160") (name "unconnected-(IC4-MIC_BIAS-Pad16)") (class "Default")
      (node (ref "IC4") (pin "16") (pinfunction "MIC_BIAS_16") (pintype "bidirectional"))
    )
    (net (code "161") (name "unconnected-(IC4-NC_1-Pad8)") (class "Default")
      (node (ref "IC4") (pin "8") (pinfunction "NC_1_8") (pintype "bidirectional"))
    )
    (net (code "162") (name "unconnected-(IC4-NC_2-Pad9)") (class "Default")
      (node (ref "IC4") (pin "9") (pinfunction "NC_2_9") (pintype "bidirectional"))
    )
    (net (code "163") (name "unconnected-(IC4-NC_3-Pad17)") (class "Default")
      (node (ref "IC4") (pin "17") (pinfunction "NC_3_17") (pintype "bidirectional"))
    )
    (net (code "164") (name "unconnected-(IC4-NC_4-Pad19)") (class "Default")
      (node (ref "IC4") (pin "19") (pinfunction "NC_4_19") (pintype "bidirectional"))
    )
    (net (code "165") (name "unconnected-(IC4-NC_5-Pad22)") (class "Default")
      (node (ref "IC4") (pin "22") (pinfunction "NC_5_22") (pintype "bidirectional"))
    )
    (net (code "166") (name "unconnected-(IC4-NC_6-Pad28)") (class "Default")
      (node (ref "IC4") (pin "28") (pinfunction "NC_6_28") (pintype "bidirectional"))
    )
    (net (code "167") (name "unconnected-(IC5-ADJ-Pad4)") (class "Default")
      (node (ref "IC5") (pin "4") (pinfunction "ADJ_4") (pintype "bidirectional"))
    )
    (net (code "168") (name "unconnected-(IC6-ADJ-Pad4)") (class "Default")
      (node (ref "IC6") (pin "4") (pinfunction "ADJ_4") (pintype "bidirectional"))
    )
    (net (code "169") (name "unconnected-(IC7-ADJ-Pad4)") (class "Default")
      (node (ref "IC7") (pin "4") (pinfunction "ADJ_4") (pintype "bidirectional"))
    )
    (net (code "170") (name "unconnected-(IC8-NC-Pad3)") (class "Default")
      (node (ref "IC8") (pin "3") (pinfunction "NC_3") (pintype "no_connect"))
    )
    (net (code "171") (name "unconnected-(J1-Pad6)") (class "Default")
      (node (ref "J1") (pin "6") (pinfunction "6_6") (pintype "bidirectional"))
    )
    (net (code "172") (name "unconnected-(J1-Pad51)") (class "Default")
      (node (ref "J1") (pin "51") (pinfunction "51_51") (pintype "bidirectional"))
    )
    (net (code "173") (name "unconnected-(J1-Pad52)") (class "Default")
      (node (ref "J1") (pin "52") (pinfunction "52_52") (pintype "bidirectional"))
    )
    (net (code "174") (name "unconnected-(J3-RING_SWITCH-Pad5)") (class "Default")
      (node (ref "J3") (pin "5") (pinfunction "RING_SWITCH_5") (pintype "bidirectional"))
    )
    (net (code "175") (name "unconnected-(J3-TIP_SWITCH-Pad4)") (class "Default")
      (node (ref "J3") (pin "4") (pinfunction "TIP_SWITCH_4") (pintype "bidirectional"))
    )
    (net (code "176") (name "unconnected-(J4-Pad1)") (class "Default")
      (node (ref "J4") (pin "1") (pinfunction "1_1") (pintype "bidirectional"))
    )
    (net (code "177") (name "unconnected-(J4-Pad2)") (class "Default")
      (node (ref "J4") (pin "2") (pinfunction "2_2") (pintype "bidirectional"))
    )
    (net (code "178") (name "unconnected-(J4-Pad3)") (class "Default")
      (node (ref "J4") (pin "3") (pinfunction "3_3") (pintype "bidirectional"))
    )
    (net (code "179") (name "unconnected-(J4-Pad4)") (class "Default")
      (node (ref "J4") (pin "4") (pinfunction "4_4") (pintype "bidirectional"))
    )
    (net (code "180") (name "unconnected-(J4-Pad5)") (class "Default")
      (node (ref "J4") (pin "5") (pinfunction "5_5") (pintype "bidirectional"))
    )
    (net (code "181") (name "unconnected-(J4-Pad6)") (class "Default")
      (node (ref "J4") (pin "6") (pinfunction "6_6") (pintype "bidirectional"))
    )
    (net (code "182") (name "unconnected-(J4-Pad7)") (class "Default")
      (node (ref "J4") (pin "7") (pinfunction "7_7") (pintype "bidirectional"))
    )
    (net (code "183") (name "unconnected-(J4-Pad21)") (class "Default")
      (node (ref "J4") (pin "21") (pinfunction "21_21") (pintype "bidirectional"))
    )
    (net (code "184") (name "unconnected-(J4-Pad22)") (class "Default")
      (node (ref "J4") (pin "22") (pinfunction "22_22") (pintype "bidirectional"))
    )
    (net (code "185") (name "unconnected-(J5-RING_SWITCH-Pad5)") (class "Default")
      (node (ref "J5") (pin "5") (pinfunction "RING_SWITCH_5") (pintype "bidirectional"))
    )
    (net (code "186") (name "unconnected-(J5-TIP_SWITCH-Pad4)") (class "Default")
      (node (ref "J5") (pin "4") (pinfunction "TIP_SWITCH_4") (pintype "bidirectional"))
    )
    (net (code "187") (name "unconnected-(J6-RING_SWITCH-Pad5)") (class "Default")
      (node (ref "J6") (pin "5") (pinfunction "RING_SWITCH_5") (pintype "bidirectional"))
    )
    (net (code "188") (name "unconnected-(J6-TIP_SWITCH-Pad4)") (class "Default")
      (node (ref "J6") (pin "4") (pinfunction "TIP_SWITCH_4") (pintype "bidirectional"))
    )
    (net (code "189") (name "unconnected-(J8-RING_SWITCH-Pad5)") (class "Default")
      (node (ref "J8") (pin "5") (pinfunction "RING_SWITCH_5") (pintype "bidirectional"))
    )
    (net (code "190") (name "unconnected-(J8-TIP_SWITCH-Pad4)") (class "Default")
      (node (ref "J8") (pin "4") (pinfunction "TIP_SWITCH_4") (pintype "bidirectional"))
    )
    (net (code "191") (name "unconnected-(J9-RING_SWITCH-Pad5)") (class "Default")
      (node (ref "J9") (pin "5") (pinfunction "RING_SWITCH_5") (pintype "bidirectional"))
    )
    (net (code "192") (name "unconnected-(J9-TIP_SWITCH-Pad4)") (class "Default")
      (node (ref "J9") (pin "4") (pinfunction "TIP_SWITCH_4") (pintype "bidirectional"))
    )
    (net (code "193") (name "unconnected-(USB1-CC1-PadA5)") (class "Default")
      (node (ref "USB1") (pin "A5") (pinfunction "CC1_A5") (pintype "bidirectional"))
    )
    (net (code "194") (name "unconnected-(USB1-CC2-PadB5)") (class "Default")
      (node (ref "USB1") (pin "B5") (pinfunction "CC2_B5") (pintype "bidirectional"))
    )
    (net (code "195") (name "unconnected-(USB1-DN1-PadA7)") (class "Default")
      (node (ref "USB1") (pin "A7") (pinfunction "DN1_A7") (pintype "bidirectional"))
    )
    (net (code "196") (name "unconnected-(USB1-DN2-PadB7)") (class "Default")
      (node (ref "USB1") (pin "B7") (pinfunction "DN2_B7") (pintype "bidirectional"))
    )
    (net (code "197") (name "unconnected-(USB1-DP1-PadA6)") (class "Default")
      (node (ref "USB1") (pin "A6") (pinfunction "DP1_A6") (pintype "bidirectional"))
    )
    (net (code "198") (name "unconnected-(USB1-DP2-PadB6)") (class "Default")
      (node (ref "USB1") (pin "B6") (pinfunction "DP2_B6") (pintype "bidirectional"))
    )
    (net (code "199") (name "unconnected-(USB1-MH1-PadP$1)") (class "Default")
      (node (ref "USB1") (pin "P$1") (pinfunction "MH1_P$1") (pintype "bidirectional"))
    )
    (net (code "200") (name "unconnected-(USB1-MH2-PadP$2)") (class "Default")
      (node (ref "USB1") (pin "P$2") (pinfunction "MH2_P$2") (pintype "bidirectional"))
    )
    (net (code "201") (name "unconnected-(USB1-MH3-PadP$3)") (class "Default")
      (node (ref "USB1") (pin "P$3") (pinfunction "MH3_P$3") (pintype "bidirectional"))
    )
    (net (code "202") (name "unconnected-(USB1-MH4-PadP$4)") (class "Default")
      (node (ref "USB1") (pin "P$4") (pinfunction "MH4_P$4") (pintype "bidirectional"))
    )
    (net (code "203") (name "unconnected-(USB1-SBU1-PadA8)") (class "Default")
      (node (ref "USB1") (pin "A8") (pinfunction "SBU1_A8") (pintype "bidirectional"))
    )
    (net (code "204") (name "unconnected-(USB1-SBU2-PadB8)") (class "Default")
      (node (ref "USB1") (pin "B8") (pinfunction "SBU2_B8") (pintype "bidirectional"))
    )
  )
)
